# Main_Board.net
KiCad netlist of a schematic drawn in Altium Designer
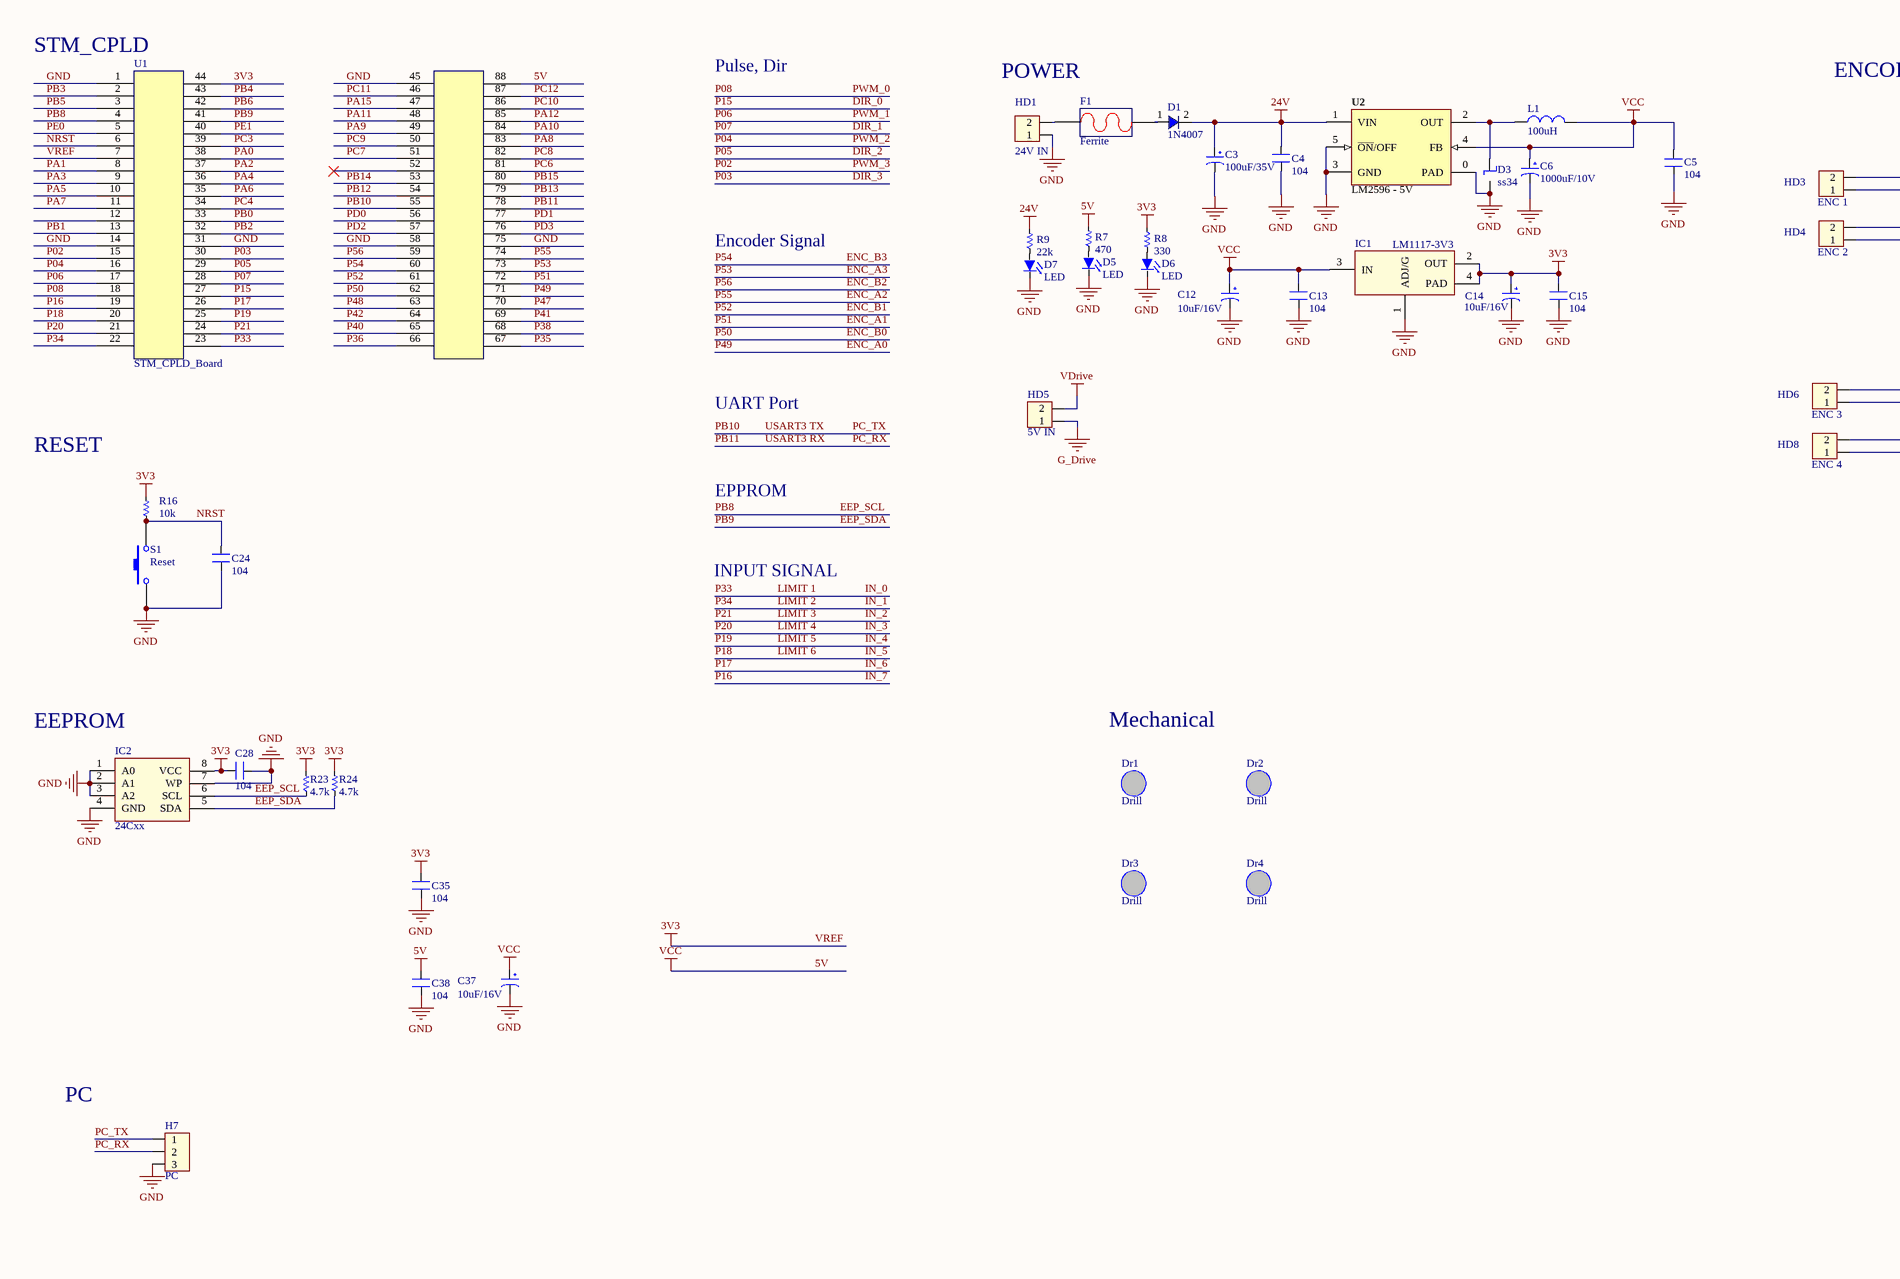
[diagram p0: Main_Board.SchDoc, top left]
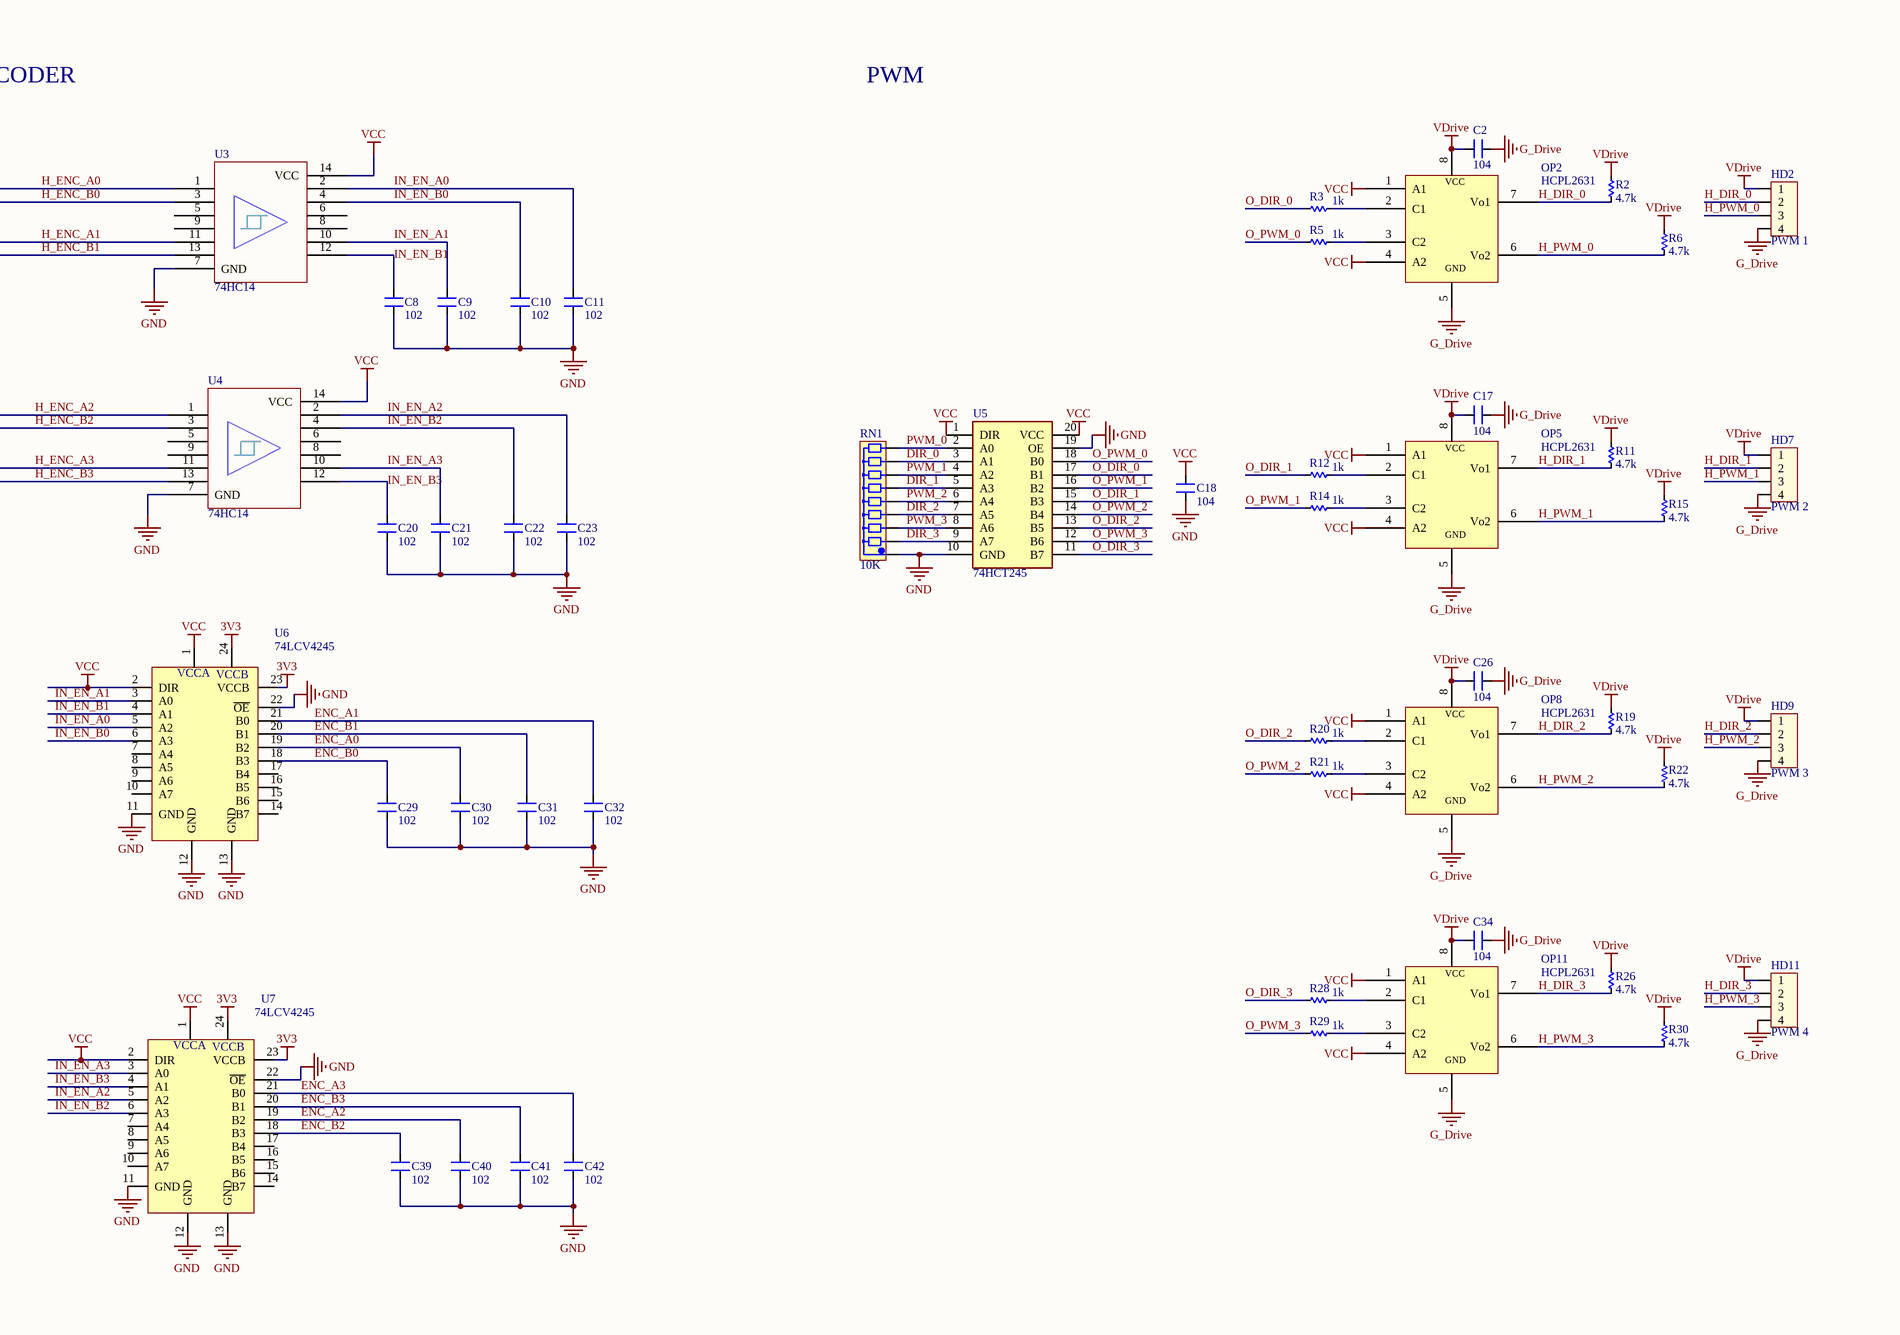
[diagram p1: Main_Board.SchDoc, top middle]
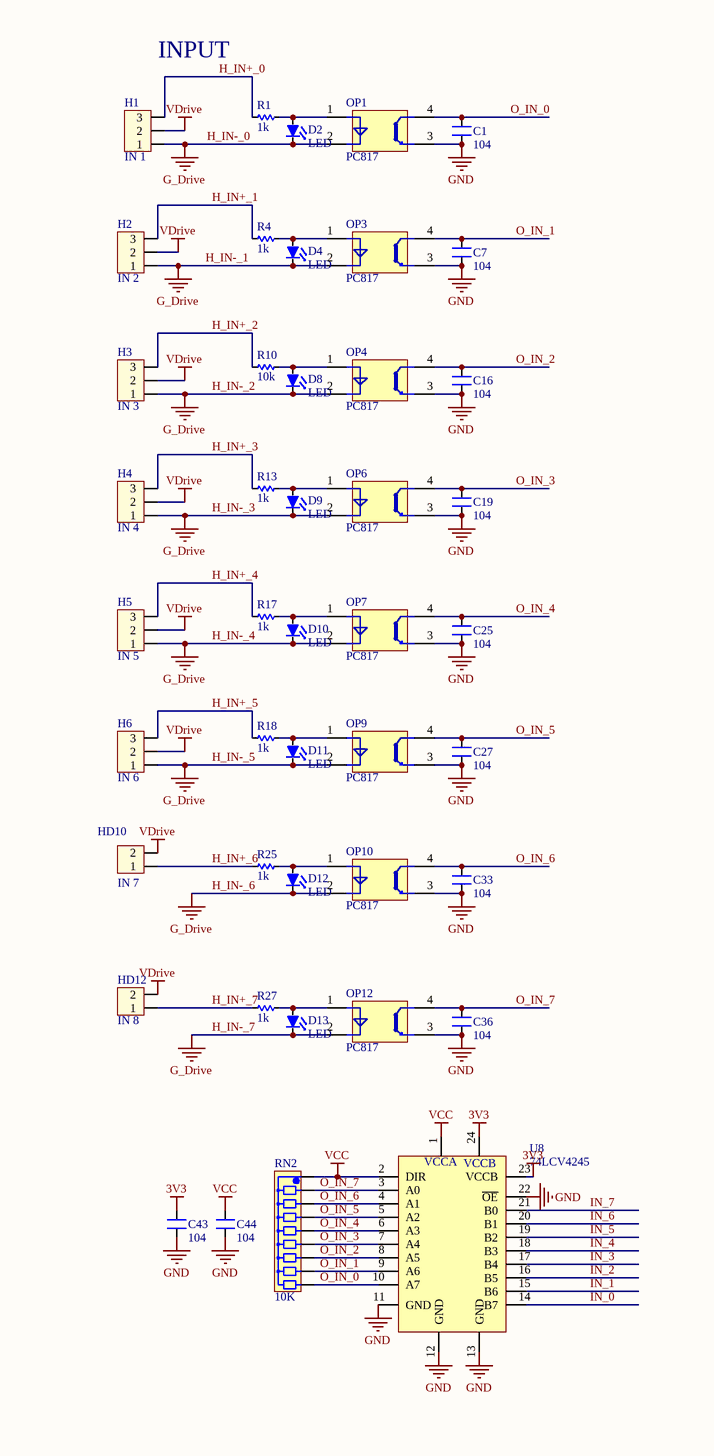
[diagram p2: Main_Board.SchDoc, top right]
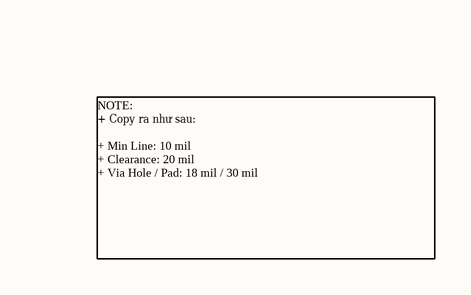
[diagram p3: Main_Board.SchDoc, bottom right]

(export (version "E")
  (design (tool "Eeschema 10.0.6"))
  (components
    (comp (ref "C1")
      (value "104")
      (footprint "CAP-SM-0805")
      (description "Ceramic Capacitor SMD")
      (libsource (lib "Main_Board") (part "CAP_SM_0805"))
    )
    (comp (ref "C2")
      (value "104")
      (footprint "CAP-SM-0805")
      (description "Ceramic Capacitor SMD")
      (libsource (lib "Main_Board") (part "CAP_SM_0805"))
    )
    (comp (ref "C3")
      (value "100uF/35V")
      (footprint "Cap_Alu_D8")
      (description "SMD Aluminum Electrolytic Capacitor")
      (libsource (lib "Main_Board") (part "Cap_SM_Alu"))
    )
    (comp (ref "C4")
      (value "104")
      (footprint "CAP-SM-0805")
      (description "Ceramic Capacitor SMD")
      (libsource (lib "Main_Board") (part "CAP_SM_0805"))
    )
    (comp (ref "C5")
      (value "104")
      (footprint "CAP-SM-0805")
      (description "Ceramic Capacitor SMD")
      (libsource (lib "Main_Board") (part "CAP_SM_0805"))
    )
    (comp (ref "C6")
      (value "1000uF/10V")
      (footprint "Cap_Alu_G")
      (description "SMD Aluminum Electrolytic Capacitor")
      (libsource (lib "Main_Board") (part "Cap_SM_Alu"))
    )
    (comp (ref "C7")
      (value "104")
      (footprint "CAP-SM-0805")
      (description "Ceramic Capacitor SMD")
      (libsource (lib "Main_Board") (part "CAP_SM_0805"))
    )
    (comp (ref "C8")
      (value "102")
      (footprint "CAP-SM-0805")
      (description "Ceramic Capacitor SMD")
      (libsource (lib "Main_Board") (part "CAP_SM_0805"))
    )
    (comp (ref "C9")
      (value "102")
      (footprint "CAP-SM-0805")
      (description "Ceramic Capacitor SMD")
      (libsource (lib "Main_Board") (part "CAP_SM_0805"))
    )
    (comp (ref "C10")
      (value "102")
      (footprint "CAP-SM-0805")
      (description "Ceramic Capacitor SMD")
      (libsource (lib "Main_Board") (part "CAP_SM_0805"))
    )
    (comp (ref "C11")
      (value "102")
      (footprint "CAP-SM-0805")
      (description "Ceramic Capacitor SMD")
      (libsource (lib "Main_Board") (part "CAP_SM_0805"))
    )
    (comp (ref "C12")
      (value "10uF/16V")
      (footprint "CAP_ALU_B")
      (description "C 47uF/50V , 220uF/16V")
      (libsource (lib "Main_Board") (part "CP2"))
    )
    (comp (ref "C13")
      (value "104")
      (footprint "CAP-SM-0805")
      (description "Ceramic Capacitor SMD")
      (libsource (lib "Main_Board") (part "CAP_SM_0805"))
    )
    (comp (ref "C14")
      (value "10uF/16V")
      (footprint "CAP_ALU_B")
      (description "C 47uF/50V , 220uF/16V")
      (libsource (lib "Main_Board") (part "CP2"))
    )
    (comp (ref "C15")
      (value "104")
      (footprint "CAP-SM-0805")
      (description "Ceramic Capacitor SMD")
      (libsource (lib "Main_Board") (part "CAP_SM_0805"))
    )
    (comp (ref "C16")
      (value "104")
      (footprint "CAP-SM-0805")
      (description "Ceramic Capacitor SMD")
      (libsource (lib "Main_Board") (part "CAP_SM_0805"))
    )
    (comp (ref "C17")
      (value "104")
      (footprint "CAP-SM-0805")
      (description "Ceramic Capacitor SMD")
      (libsource (lib "Main_Board") (part "CAP_SM_0805"))
    )
    (comp (ref "C18")
      (value "104")
      (footprint "CAP-SM-0805")
      (description "Ceramic Capacitor SMD")
      (libsource (lib "Main_Board") (part "CAP_SM_0805"))
    )
    (comp (ref "C19")
      (value "104")
      (footprint "CAP-SM-0805")
      (description "Ceramic Capacitor SMD")
      (libsource (lib "Main_Board") (part "CAP_SM_0805"))
    )
    (comp (ref "C20")
      (value "102")
      (footprint "CAP-SM-0805")
      (description "Ceramic Capacitor SMD")
      (libsource (lib "Main_Board") (part "CAP_SM_0805"))
    )
    (comp (ref "C21")
      (value "102")
      (footprint "CAP-SM-0805")
      (description "Ceramic Capacitor SMD")
      (libsource (lib "Main_Board") (part "CAP_SM_0805"))
    )
    (comp (ref "C22")
      (value "102")
      (footprint "CAP-SM-0805")
      (description "Ceramic Capacitor SMD")
      (libsource (lib "Main_Board") (part "CAP_SM_0805"))
    )
    (comp (ref "C23")
      (value "102")
      (footprint "CAP-SM-0805")
      (description "Ceramic Capacitor SMD")
      (libsource (lib "Main_Board") (part "CAP_SM_0805"))
    )
    (comp (ref "C24")
      (value "104")
      (footprint "CAP-SM-0805")
      (description "Ceramic Capacitor SMD")
      (libsource (lib "Main_Board") (part "CAP_SM_0805"))
    )
    (comp (ref "C25")
      (value "104")
      (footprint "CAP-SM-0805")
      (description "Ceramic Capacitor SMD")
      (libsource (lib "Main_Board") (part "CAP_SM_0805"))
    )
    (comp (ref "C26")
      (value "104")
      (footprint "CAP-SM-0805")
      (description "Ceramic Capacitor SMD")
      (libsource (lib "Main_Board") (part "CAP_SM_0805"))
    )
    (comp (ref "C27")
      (value "104")
      (footprint "CAP-SM-0805")
      (description "Ceramic Capacitor SMD")
      (libsource (lib "Main_Board") (part "CAP_SM_0805"))
    )
    (comp (ref "C28")
      (value "104")
      (footprint "CAP-SM-0805")
      (description "Ceramic Capacitor SMD")
      (libsource (lib "Main_Board") (part "CAP_SM_0805"))
    )
    (comp (ref "C29")
      (value "102")
      (footprint "CAP-SM-0805")
      (description "Ceramic Capacitor SMD")
      (libsource (lib "Main_Board") (part "CAP_SM_0805"))
    )
    (comp (ref "C30")
      (value "102")
      (footprint "CAP-SM-0805")
      (description "Ceramic Capacitor SMD")
      (libsource (lib "Main_Board") (part "CAP_SM_0805"))
    )
    (comp (ref "C31")
      (value "102")
      (footprint "CAP-SM-0805")
      (description "Ceramic Capacitor SMD")
      (libsource (lib "Main_Board") (part "CAP_SM_0805"))
    )
    (comp (ref "C32")
      (value "102")
      (footprint "CAP-SM-0805")
      (description "Ceramic Capacitor SMD")
      (libsource (lib "Main_Board") (part "CAP_SM_0805"))
    )
    (comp (ref "C33")
      (value "104")
      (footprint "CAP-SM-0805")
      (description "Ceramic Capacitor SMD")
      (libsource (lib "Main_Board") (part "CAP_SM_0805"))
    )
    (comp (ref "C34")
      (value "104")
      (footprint "CAP-SM-0805")
      (description "Ceramic Capacitor SMD")
      (libsource (lib "Main_Board") (part "CAP_SM_0805"))
    )
    (comp (ref "C35")
      (value "104")
      (footprint "CAP-SM-0805")
      (description "Ceramic Capacitor SMD")
      (libsource (lib "Main_Board") (part "CAP_SM_0805"))
    )
    (comp (ref "C36")
      (value "104")
      (footprint "CAP-SM-0805")
      (description "Ceramic Capacitor SMD")
      (libsource (lib "Main_Board") (part "CAP_SM_0805"))
    )
    (comp (ref "C37")
      (value "10uF/16V")
      (footprint "CAP_ALU_B")
      (description "C 47uF/50V , 220uF/16V")
      (libsource (lib "Main_Board") (part "CP2"))
    )
    (comp (ref "C38")
      (value "104")
      (footprint "CAP-SM-0805")
      (description "Ceramic Capacitor SMD")
      (libsource (lib "Main_Board") (part "CAP_SM_0805"))
    )
    (comp (ref "C39")
      (value "102")
      (footprint "CAP-SM-0805")
      (description "Ceramic Capacitor SMD")
      (libsource (lib "Main_Board") (part "CAP_SM_0805"))
    )
    (comp (ref "C40")
      (value "102")
      (footprint "CAP-SM-0805")
      (description "Ceramic Capacitor SMD")
      (libsource (lib "Main_Board") (part "CAP_SM_0805"))
    )
    (comp (ref "C41")
      (value "102")
      (footprint "CAP-SM-0805")
      (description "Ceramic Capacitor SMD")
      (libsource (lib "Main_Board") (part "CAP_SM_0805"))
    )
    (comp (ref "C42")
      (value "102")
      (footprint "CAP-SM-0805")
      (description "Ceramic Capacitor SMD")
      (libsource (lib "Main_Board") (part "CAP_SM_0805"))
    )
    (comp (ref "C43")
      (value "104")
      (footprint "CAP-SM-0805")
      (description "Ceramic Capacitor SMD")
      (libsource (lib "Main_Board") (part "CAP_SM_0805"))
    )
    (comp (ref "C44")
      (value "104")
      (footprint "CAP-SM-0805")
      (description "Ceramic Capacitor SMD")
      (libsource (lib "Main_Board") (part "CAP_SM_0805"))
    )
    (comp (ref "D1")
      (value "1N4007")
      (footprint "DO-214AB")
      (description "General Rectifier")
      (libsource (lib "Main_Board") (part "Diode"))
    )
    (comp (ref "D2")
      (value "LED")
      (footprint "LED_0805_Blue")
      (description "LED SMD")
      (libsource (lib "Main_Board") (part "LED_SMD"))
    )
    (comp (ref "D3")
      (value "ss34")
      (footprint "DO-214AB")
      (description "Surface Mount Schottky Barrier Rectifier")
      (libsource (lib "Main_Board") (part "ss34"))
    )
    (comp (ref "D4")
      (value "LED")
      (footprint "LED_0805_Blue")
      (description "LED SMD")
      (libsource (lib "Main_Board") (part "LED_SMD"))
    )
    (comp (ref "D5")
      (value "LED")
      (footprint "LED_0805_Blue")
      (description "LED SMD")
      (libsource (lib "Main_Board") (part "LED_SMD"))
    )
    (comp (ref "D6")
      (value "LED")
      (footprint "LED_0805_Blue")
      (description "LED SMD")
      (libsource (lib "Main_Board") (part "LED_SMD"))
    )
    (comp (ref "D7")
      (value "LED")
      (footprint "LED_0805_Blue")
      (description "LED SMD")
      (libsource (lib "Main_Board") (part "LED_SMD"))
    )
    (comp (ref "D8")
      (value "LED")
      (footprint "LED_0805_Blue")
      (description "LED SMD")
      (libsource (lib "Main_Board") (part "LED_SMD"))
    )
    (comp (ref "D9")
      (value "LED")
      (footprint "LED_0805_Blue")
      (description "LED SMD")
      (libsource (lib "Main_Board") (part "LED_SMD"))
    )
    (comp (ref "D10")
      (value "LED")
      (footprint "LED_0805_Blue")
      (description "LED SMD")
      (libsource (lib "Main_Board") (part "LED_SMD"))
    )
    (comp (ref "D11")
      (value "LED")
      (footprint "LED_0805_Blue")
      (description "LED SMD")
      (libsource (lib "Main_Board") (part "LED_SMD"))
    )
    (comp (ref "D12")
      (value "LED")
      (footprint "LED_0805_Blue")
      (description "LED SMD")
      (libsource (lib "Main_Board") (part "LED_SMD"))
    )
    (comp (ref "D13")
      (value "LED")
      (footprint "LED_0805_Blue")
      (description "LED SMD")
      (libsource (lib "Main_Board") (part "LED_SMD"))
    )
    (comp (ref "Dr1")
      (value "Drill")
      (footprint "Drill 3mm")
      (description "Drill 3mm")
      (libsource (lib "Main_Board") (part "Drill 3mm"))
    )
    (comp (ref "Dr2")
      (value "Drill")
      (footprint "Drill 3mm")
      (description "Drill 3mm")
      (libsource (lib "Main_Board") (part "Drill 3mm"))
    )
    (comp (ref "Dr3")
      (value "Drill")
      (footprint "Drill 3mm")
      (description "Drill 3mm")
      (libsource (lib "Main_Board") (part "Drill 3mm"))
    )
    (comp (ref "Dr4")
      (value "Drill")
      (footprint "Drill 3mm")
      (description "Drill 3mm")
      (libsource (lib "Main_Board") (part "Drill 3mm"))
    )
    (comp (ref "F1")
      (value "Ferrite")
      (footprint "Ferrite")
      (description "Ferrite bead")
      (libsource (lib "Main_Board") (part "Ferrite bead"))
    )
    (comp (ref "H1")
      (value "IN 1")
      (footprint "Header White 3")
      (description "Connector 3")
      (libsource (lib "") (part "Header white 3_1"))
    )
    (comp (ref "H2")
      (value "IN 2")
      (footprint "Header White 3")
      (description "Connector 3")
      (libsource (lib "") (part "Header white 3_1"))
    )
    (comp (ref "H3")
      (value "IN 3")
      (footprint "Header White 3")
      (description "Connector 3")
      (libsource (lib "") (part "Header white 3_1"))
    )
    (comp (ref "H4")
      (value "IN 4")
      (footprint "Header White 3")
      (description "Connector 3")
      (libsource (lib "") (part "Header white 3_1"))
    )
    (comp (ref "H5")
      (value "IN 5")
      (footprint "Header White 3")
      (description "Connector 3")
      (libsource (lib "") (part "Header white 3_1"))
    )
    (comp (ref "H6")
      (value "IN 6")
      (footprint "Header White 3")
      (description "Connector 3")
      (libsource (lib "") (part "Header white 3_1"))
    )
    (comp (ref "H7")
      (value "PC")
      (footprint "Header White 3")
      (description "Connector 3")
      (libsource (lib "Main_Board") (part "Header white 3"))
    )
    (comp (ref "HD1")
      (value "24V IN")
      (footprint "Domino 2")
      (description "Domino 2 200mil")
      (libsource (lib "Main_Board") (part "Domino 2"))
    )
    (comp (ref "HD2")
      (value "PWM 1")
      (footprint "Domino 4")
      (description "Domino 4 200mil")
      (libsource (lib "Main_Board") (part "Domino 4"))
    )
    (comp (ref "HD3")
      (value "ENC 1")
      (footprint "Domino 2")
      (description "Domino 2 200mil")
      (libsource (lib "Main_Board") (part "Domino 2"))
    )
    (comp (ref "HD4")
      (value "ENC 2")
      (footprint "Domino 2")
      (description "Domino 2 200mil")
      (libsource (lib "Main_Board") (part "Domino 2"))
    )
    (comp (ref "HD5")
      (value "5V IN")
      (footprint "Domino 2")
      (description "Domino 2 200mil")
      (libsource (lib "Main_Board") (part "Domino 2"))
    )
    (comp (ref "HD6")
      (value "ENC 3")
      (footprint "Domino 2")
      (description "Domino 2 200mil")
      (libsource (lib "Main_Board") (part "Domino 2"))
    )
    (comp (ref "HD7")
      (value "PWM 2")
      (footprint "Domino 4")
      (description "Domino 4 200mil")
      (libsource (lib "Main_Board") (part "Domino 4"))
    )
    (comp (ref "HD8")
      (value "ENC 4")
      (footprint "Domino 2")
      (description "Domino 2 200mil")
      (libsource (lib "Main_Board") (part "Domino 2"))
    )
    (comp (ref "HD9")
      (value "PWM 3")
      (footprint "Domino 4")
      (description "Domino 4 200mil")
      (libsource (lib "Main_Board") (part "Domino 4"))
    )
    (comp (ref "HD10")
      (value "IN 7")
      (footprint "Domino 2")
      (description "Domino 2 200mil")
      (libsource (lib "Main_Board") (part "Domino 2"))
    )
    (comp (ref "HD11")
      (value "PWM 4")
      (footprint "Domino 4")
      (description "Domino 4 200mil")
      (libsource (lib "Main_Board") (part "Domino 4"))
    )
    (comp (ref "HD12")
      (value "IN 8")
      (footprint "Domino 2")
      (description "Domino 2 200mil")
      (libsource (lib "Main_Board") (part "Domino 2"))
    )
    (comp (ref "IC1")
      (value "LM1117-3V3")
      (footprint "SOT223-4N")
      (description "Available in 1.8V, 2.5V, 2.85V, 3.3V, 5V, and  Adjustable Versions")
      (libsource (lib "Main_Board") (part "LM1117"))
    )
    (comp (ref "IC2")
      (value "24Cxx")
      (footprint "SOIC8")
      (description "Standard 2-Wire Bus Interface Serial EEPROM")
      (fields (field (name "COPYRIGHT BY") "VanDungEvn"))
      (libsource (lib "Main_Board") (part "24Cxx"))
    )
    (comp (ref "L1")
      (value "100uH")
      (footprint "INDUCTOR_SMD")
      (description "Inductor")
      (libsource (lib "Main_Board") (part "L1"))
    )
    (comp (ref "OP1")
      (value "PC817")
      (footprint "SOP4 2.54")
      (description "OPTO")
      (libsource (lib "Main_Board") (part "PC817"))
    )
    (comp (ref "OP2")
      (value "HCPL2631")
      (footprint "6N137SMD")
      (description "High CMR, High Speed TTL Compatible Optocouplers")
      (libsource (lib "Main_Board") (part "HCPL2631"))
    )
    (comp (ref "OP3")
      (value "PC817")
      (footprint "SOP4 2.54")
      (description "OPTO")
      (libsource (lib "Main_Board") (part "PC817"))
    )
    (comp (ref "OP4")
      (value "PC817")
      (footprint "SOP4 2.54")
      (description "OPTO")
      (libsource (lib "Main_Board") (part "PC817"))
    )
    (comp (ref "OP5")
      (value "HCPL2631")
      (footprint "6N137SMD")
      (description "High CMR, High Speed TTL Compatible Optocouplers")
      (libsource (lib "Main_Board") (part "HCPL2631"))
    )
    (comp (ref "OP6")
      (value "PC817")
      (footprint "SOP4 2.54")
      (description "OPTO")
      (libsource (lib "Main_Board") (part "PC817"))
    )
    (comp (ref "OP7")
      (value "PC817")
      (footprint "SOP4 2.54")
      (description "OPTO")
      (libsource (lib "Main_Board") (part "PC817"))
    )
    (comp (ref "OP8")
      (value "HCPL2631")
      (footprint "6N137SMD")
      (description "High CMR, High Speed TTL Compatible Optocouplers")
      (libsource (lib "Main_Board") (part "HCPL2631"))
    )
    (comp (ref "OP9")
      (value "PC817")
      (footprint "SOP4 2.54")
      (description "OPTO")
      (libsource (lib "Main_Board") (part "PC817"))
    )
    (comp (ref "OP10")
      (value "PC817")
      (footprint "SOP4 2.54")
      (description "OPTO")
      (libsource (lib "Main_Board") (part "PC817"))
    )
    (comp (ref "OP11")
      (value "HCPL2631")
      (footprint "6N137SMD")
      (description "High CMR, High Speed TTL Compatible Optocouplers")
      (libsource (lib "Main_Board") (part "HCPL2631"))
    )
    (comp (ref "OP12")
      (value "PC817")
      (footprint "SOP4 2.54")
      (description "OPTO")
      (libsource (lib "Main_Board") (part "PC817"))
    )
    (comp (ref "R1")
      (value "1k")
      (footprint "RES-SM-0805")
      (description "Resistor")
      (fields
        (field (name "MANUFACTURER") "Generic Components")
        (field (name "PUBLISHER") "Altium Hobart Technology Centre")
      )
      (libsource (lib "Main_Board") (part "Res-SMD"))
    )
    (comp (ref "R2")
      (value "4.7k")
      (footprint "RES-SM-0805")
      (description "Resistor")
      (fields
        (field (name "MANUFACTURER") "Generic Components")
        (field (name "PUBLISHER") "Altium Hobart Technology Centre")
      )
      (libsource (lib "Main_Board") (part "Res-SMD"))
    )
    (comp (ref "R3")
      (value "1k")
      (footprint "RES-SM-0805")
      (description "Resistor")
      (fields
        (field (name "MANUFACTURER") "Generic Components")
        (field (name "PUBLISHER") "Altium Hobart Technology Centre")
      )
      (libsource (lib "Main_Board") (part "Res-SMD"))
    )
    (comp (ref "R4")
      (value "1k")
      (footprint "RES-SM-0805")
      (description "Resistor")
      (fields
        (field (name "MANUFACTURER") "Generic Components")
        (field (name "PUBLISHER") "Altium Hobart Technology Centre")
      )
      (libsource (lib "Main_Board") (part "Res-SMD"))
    )
    (comp (ref "R5")
      (value "1k")
      (footprint "RES-SM-0805")
      (description "Resistor")
      (fields
        (field (name "MANUFACTURER") "Generic Components")
        (field (name "PUBLISHER") "Altium Hobart Technology Centre")
      )
      (libsource (lib "Main_Board") (part "Res-SMD"))
    )
    (comp (ref "R6")
      (value "4.7k")
      (footprint "RES-SM-0805")
      (description "Resistor")
      (fields
        (field (name "MANUFACTURER") "Generic Components")
        (field (name "PUBLISHER") "Altium Hobart Technology Centre")
      )
      (libsource (lib "Main_Board") (part "Res-SMD"))
    )
    (comp (ref "R7")
      (value "470")
      (footprint "RES-SM-0805")
      (description "Resistor")
      (fields
        (field (name "MANUFACTURER") "Generic Components")
        (field (name "PUBLISHER") "Altium Hobart Technology Centre")
      )
      (libsource (lib "Main_Board") (part "Res-SMD"))
    )
    (comp (ref "R8")
      (value "330")
      (footprint "RES-SM-0805")
      (description "Resistor")
      (fields
        (field (name "MANUFACTURER") "Generic Components")
        (field (name "PUBLISHER") "Altium Hobart Technology Centre")
      )
      (libsource (lib "Main_Board") (part "Res-SMD"))
    )
    (comp (ref "R9")
      (value "22k")
      (footprint "RES-SM-0805")
      (description "Resistor")
      (fields
        (field (name "MANUFACTURER") "Generic Components")
        (field (name "PUBLISHER") "Altium Hobart Technology Centre")
      )
      (libsource (lib "Main_Board") (part "Res-SMD"))
    )
    (comp (ref "R10")
      (value "10k")
      (footprint "RES-SM-0805")
      (description "Resistor")
      (fields
        (field (name "MANUFACTURER") "Generic Components")
        (field (name "PUBLISHER") "Altium Hobart Technology Centre")
      )
      (libsource (lib "Main_Board") (part "Res-SMD"))
    )
    (comp (ref "R11")
      (value "4.7k")
      (footprint "RES-SM-0805")
      (description "Resistor")
      (fields
        (field (name "MANUFACTURER") "Generic Components")
        (field (name "PUBLISHER") "Altium Hobart Technology Centre")
      )
      (libsource (lib "Main_Board") (part "Res-SMD"))
    )
    (comp (ref "R12")
      (value "1k")
      (footprint "RES-SM-0805")
      (description "Resistor")
      (fields
        (field (name "MANUFACTURER") "Generic Components")
        (field (name "PUBLISHER") "Altium Hobart Technology Centre")
      )
      (libsource (lib "Main_Board") (part "Res-SMD"))
    )
    (comp (ref "R13")
      (value "1k")
      (footprint "RES-SM-0805")
      (description "Resistor")
      (fields
        (field (name "MANUFACTURER") "Generic Components")
        (field (name "PUBLISHER") "Altium Hobart Technology Centre")
      )
      (libsource (lib "Main_Board") (part "Res-SMD"))
    )
    (comp (ref "R14")
      (value "1k")
      (footprint "RES-SM-0805")
      (description "Resistor")
      (fields
        (field (name "MANUFACTURER") "Generic Components")
        (field (name "PUBLISHER") "Altium Hobart Technology Centre")
      )
      (libsource (lib "Main_Board") (part "Res-SMD"))
    )
    (comp (ref "R15")
      (value "4.7k")
      (footprint "RES-SM-0805")
      (description "Resistor")
      (fields
        (field (name "MANUFACTURER") "Generic Components")
        (field (name "PUBLISHER") "Altium Hobart Technology Centre")
      )
      (libsource (lib "Main_Board") (part "Res-SMD"))
    )
    (comp (ref "R16")
      (value "10k")
      (footprint "RES-SM-0805")
      (description "Resistor")
      (fields
        (field (name "MANUFACTURER") "Generic Components")
        (field (name "PUBLISHER") "Altium Hobart Technology Centre")
      )
      (libsource (lib "Main_Board") (part "Res-SMD"))
    )
    (comp (ref "R17")
      (value "1k")
      (footprint "RES-SM-0805")
      (description "Resistor")
      (fields
        (field (name "MANUFACTURER") "Generic Components")
        (field (name "PUBLISHER") "Altium Hobart Technology Centre")
      )
      (libsource (lib "Main_Board") (part "Res-SMD"))
    )
    (comp (ref "R18")
      (value "1k")
      (footprint "RES-SM-0805")
      (description "Resistor")
      (fields
        (field (name "MANUFACTURER") "Generic Components")
        (field (name "PUBLISHER") "Altium Hobart Technology Centre")
      )
      (libsource (lib "Main_Board") (part "Res-SMD"))
    )
    (comp (ref "R19")
      (value "4.7k")
      (footprint "RES-SM-0805")
      (description "Resistor")
      (fields
        (field (name "MANUFACTURER") "Generic Components")
        (field (name "PUBLISHER") "Altium Hobart Technology Centre")
      )
      (libsource (lib "Main_Board") (part "Res-SMD"))
    )
    (comp (ref "R20")
      (value "1k")
      (footprint "RES-SM-0805")
      (description "Resistor")
      (fields
        (field (name "MANUFACTURER") "Generic Components")
        (field (name "PUBLISHER") "Altium Hobart Technology Centre")
      )
      (libsource (lib "Main_Board") (part "Res-SMD"))
    )
    (comp (ref "R21")
      (value "1k")
      (footprint "RES-SM-0805")
      (description "Resistor")
      (fields
        (field (name "MANUFACTURER") "Generic Components")
        (field (name "PUBLISHER") "Altium Hobart Technology Centre")
      )
      (libsource (lib "Main_Board") (part "Res-SMD"))
    )
    (comp (ref "R22")
      (value "4.7k")
      (footprint "RES-SM-0805")
      (description "Resistor")
      (fields
        (field (name "MANUFACTURER") "Generic Components")
        (field (name "PUBLISHER") "Altium Hobart Technology Centre")
      )
      (libsource (lib "Main_Board") (part "Res-SMD"))
    )
    (comp (ref "R23")
      (value "4.7k")
      (footprint "RES-SM-0805")
      (description "Resistor")
      (fields
        (field (name "MANUFACTURER") "Generic Components")
        (field (name "PUBLISHER") "Altium Hobart Technology Centre")
      )
      (libsource (lib "Main_Board") (part "Res-SMD"))
    )
    (comp (ref "R24")
      (value "4.7k")
      (footprint "RES-SM-0805")
      (description "Resistor")
      (fields
        (field (name "MANUFACTURER") "Generic Components")
        (field (name "PUBLISHER") "Altium Hobart Technology Centre")
      )
      (libsource (lib "Main_Board") (part "Res-SMD"))
    )
    (comp (ref "R25")
      (value "1k")
      (footprint "RES-SM-0805")
      (description "Resistor")
      (fields
        (field (name "MANUFACTURER") "Generic Components")
        (field (name "PUBLISHER") "Altium Hobart Technology Centre")
      )
      (libsource (lib "Main_Board") (part "Res-SMD"))
    )
    (comp (ref "R26")
      (value "4.7k")
      (footprint "RES-SM-0805")
      (description "Resistor")
      (fields
        (field (name "MANUFACTURER") "Generic Components")
        (field (name "PUBLISHER") "Altium Hobart Technology Centre")
      )
      (libsource (lib "Main_Board") (part "Res-SMD"))
    )
    (comp (ref "R27")
      (value "1k")
      (footprint "RES-SM-0805")
      (description "Resistor")
      (fields
        (field (name "MANUFACTURER") "Generic Components")
        (field (name "PUBLISHER") "Altium Hobart Technology Centre")
      )
      (libsource (lib "Main_Board") (part "Res-SMD"))
    )
    (comp (ref "R28")
      (value "1k")
      (footprint "RES-SM-0805")
      (description "Resistor")
      (fields
        (field (name "MANUFACTURER") "Generic Components")
        (field (name "PUBLISHER") "Altium Hobart Technology Centre")
      )
      (libsource (lib "Main_Board") (part "Res-SMD"))
    )
    (comp (ref "R29")
      (value "1k")
      (footprint "RES-SM-0805")
      (description "Resistor")
      (fields
        (field (name "MANUFACTURER") "Generic Components")
        (field (name "PUBLISHER") "Altium Hobart Technology Centre")
      )
      (libsource (lib "Main_Board") (part "Res-SMD"))
    )
    (comp (ref "R30")
      (value "4.7k")
      (footprint "RES-SM-0805")
      (description "Resistor")
      (fields
        (field (name "MANUFACTURER") "Generic Components")
        (field (name "PUBLISHER") "Altium Hobart Technology Centre")
      )
      (libsource (lib "Main_Board") (part "Res-SMD"))
    )
    (comp (ref "RN1")
      (value "10K")
      (footprint "RN8")
      (description "Resistor 8 (Thanh)")
      (libsource (lib "Main_Board") (part "RN8"))
    )
    (comp (ref "RN2")
      (value "10K")
      (footprint "RN8")
      (description "Resistor 8 (Thanh)")
      (libsource (lib "") (part "RN8_1"))
    )
    (comp (ref "S1")
      (value "Reset")
      (footprint "SW2")
      (description "Switch button 2 pin")
      (libsource (lib "Main_Board") (part "SW - 2Pin"))
    )
    (comp (ref "U1")
      (value "STM_CPLD_Board")
      (footprint "STM_CPLD_Board")
      (description "STM32f4 and Max2 570 on one board")
      (libsource (lib "Main_Board") (part "STM_CPLD_Board"))
    )
    (comp (ref "U2")
      (value "LM2596 - 5V")
      (footprint "TO263")
      (description "SIMPLE SWITCHER® Power Converter 150-kHz - 3A Step-Down Voltage Regulator")
      (libsource (lib "Main_Board") (part "LM2596"))
    )
    (comp (ref "U3")
      (value "74HC14")
      (footprint "SO14-150mil")
      (description "Hex Inverters With SCHMITT-TRIGGER Inputs")
      (libsource (lib "Main_Board") (part "74HC14"))
    )
    (comp (ref "U4")
      (value "74HC14")
      (footprint "SO14-150mil")
      (description "Hex Inverters With SCHMITT-TRIGGER Inputs")
      (libsource (lib "Main_Board") (part "74HC14"))
    )
    (comp (ref "U5")
      (value "74HCT245")
      (footprint "soic20")
      (description "Octal bus tranceiver")
      (libsource (lib "Main_Board") (part "74HC245"))
    )
    (comp (ref "U6")
      (value "74LCV4245")
      (footprint "SOIC24 - wide")
      (description "Octal dual supply translating transceiver; 3-state")
      (libsource (lib "Main_Board") (part "74LCV4245"))
    )
    (comp (ref "U7")
      (value "74LCV4245")
      (footprint "SOIC24 - wide")
      (description "Octal dual supply translating transceiver; 3-state")
      (libsource (lib "Main_Board") (part "74LCV4245"))
    )
    (comp (ref "U8")
      (value "74LCV4245")
      (footprint "SOIC24 - wide")
      (description "Octal dual supply translating transceiver; 3-state")
      (libsource (lib "Main_Board") (part "74LCV4245"))
    )
  )
  (nets
    (net (code "1") (name "/DIR_0") (class "Default")
      (node (ref "RN1") (pin "8") (pinfunction "8_8") (pintype "passive"))
      (node (ref "U1") (pin "27") (pinfunction "27_27") (pintype "passive"))
      (node (ref "U5") (pin "3") (pinfunction "A1_3") (pintype "passive"))
    )
    (net (code "2") (name "/DIR_1") (class "Default")
      (node (ref "RN1") (pin "6") (pinfunction "6_6") (pintype "passive"))
      (node (ref "U1") (pin "28") (pinfunction "28_28") (pintype "passive"))
      (node (ref "U5") (pin "5") (pinfunction "A3_5") (pintype "passive"))
    )
    (net (code "3") (name "/DIR_2") (class "Default")
      (node (ref "RN1") (pin "4") (pinfunction "4_4") (pintype "passive"))
      (node (ref "U1") (pin "29") (pinfunction "29_29") (pintype "passive"))
      (node (ref "U5") (pin "7") (pinfunction "A5_7") (pintype "passive"))
    )
    (net (code "4") (name "/DIR_3") (class "Default")
      (node (ref "RN1") (pin "2") (pinfunction "2_2") (pintype "passive"))
      (node (ref "U1") (pin "30") (pinfunction "30_30") (pintype "passive"))
      (node (ref "U5") (pin "9") (pinfunction "A7_9") (pintype "passive"))
    )
    (net (code "5") (name "/EEP_SCL") (class "Default")
      (node (ref "IC2") (pin "6") (pinfunction "SCL_6") (pintype "passive"))
      (node (ref "R23") (pin "1") (pinfunction "1_1") (pintype "passive"))
      (node (ref "U1") (pin "4") (pinfunction "4_4") (pintype "passive"))
    )
    (net (code "6") (name "/EEP_SDA") (class "Default")
      (node (ref "IC2") (pin "5") (pinfunction "SDA_5") (pintype "passive"))
      (node (ref "R24") (pin "2") (pinfunction "2_2") (pintype "passive"))
      (node (ref "U1") (pin "41") (pinfunction "41_41") (pintype "passive"))
    )
    (net (code "7") (name "/ENC_A0") (class "Default")
      (node (ref "C30") (pin "2") (pinfunction "2_2") (pintype "passive"))
      (node (ref "U1") (pin "71") (pinfunction "71_71") (pintype "passive"))
      (node (ref "U6") (pin "19") (pinfunction "B2_19") (pintype "passive"))
    )
    (net (code "8") (name "/ENC_A1") (class "Default")
      (node (ref "C32") (pin "2") (pinfunction "2_2") (pintype "passive"))
      (node (ref "U1") (pin "72") (pinfunction "72_72") (pintype "passive"))
      (node (ref "U6") (pin "21") (pinfunction "B0_21") (pintype "passive"))
    )
    (net (code "9") (name "/ENC_A2") (class "Default")
      (node (ref "C40") (pin "2") (pinfunction "2_2") (pintype "passive"))
      (node (ref "U1") (pin "74") (pinfunction "74_74") (pintype "passive"))
      (node (ref "U7") (pin "19") (pinfunction "B2_19") (pintype "passive"))
    )
    (net (code "10") (name "/ENC_A3") (class "Default")
      (node (ref "C42") (pin "2") (pinfunction "2_2") (pintype "passive"))
      (node (ref "U1") (pin "73") (pinfunction "73_73") (pintype "passive"))
      (node (ref "U7") (pin "21") (pinfunction "B0_21") (pintype "passive"))
    )
    (net (code "11") (name "/ENC_B0") (class "Default")
      (node (ref "C29") (pin "2") (pinfunction "2_2") (pintype "passive"))
      (node (ref "U1") (pin "62") (pinfunction "62_62") (pintype "passive"))
      (node (ref "U6") (pin "18") (pinfunction "B3_18") (pintype "passive"))
    )
    (net (code "12") (name "/ENC_B1") (class "Default")
      (node (ref "C31") (pin "2") (pinfunction "2_2") (pintype "passive"))
      (node (ref "U1") (pin "61") (pinfunction "61_61") (pintype "passive"))
      (node (ref "U6") (pin "20") (pinfunction "B1_20") (pintype "passive"))
    )
    (net (code "13") (name "/ENC_B2") (class "Default")
      (node (ref "C39") (pin "2") (pinfunction "2_2") (pintype "passive"))
      (node (ref "U1") (pin "59") (pinfunction "59_59") (pintype "passive"))
      (node (ref "U7") (pin "18") (pinfunction "B3_18") (pintype "passive"))
    )
    (net (code "14") (name "/ENC_B3") (class "Default")
      (node (ref "C41") (pin "2") (pinfunction "2_2") (pintype "passive"))
      (node (ref "U1") (pin "60") (pinfunction "60_60") (pintype "passive"))
      (node (ref "U7") (pin "20") (pinfunction "B1_20") (pintype "passive"))
    )
    (net (code "15") (name "/H_DIR_0") (class "Default")
      (node (ref "HD2") (pin "2") (pinfunction "2_2") (pintype "passive"))
      (node (ref "OP2") (pin "7") (pinfunction "Vo1_7") (pintype "passive"))
      (node (ref "R2") (pin "2") (pinfunction "2_2") (pintype "passive"))
    )
    (net (code "16") (name "/H_DIR_1") (class "Default")
      (node (ref "HD7") (pin "2") (pinfunction "2_2") (pintype "passive"))
      (node (ref "OP5") (pin "7") (pinfunction "Vo1_7") (pintype "passive"))
      (node (ref "R11") (pin "2") (pinfunction "2_2") (pintype "passive"))
    )
    (net (code "17") (name "/H_DIR_2") (class "Default")
      (node (ref "HD9") (pin "2") (pinfunction "2_2") (pintype "passive"))
      (node (ref "OP8") (pin "7") (pinfunction "Vo1_7") (pintype "passive"))
      (node (ref "R19") (pin "2") (pinfunction "2_2") (pintype "passive"))
    )
    (net (code "18") (name "/H_DIR_3") (class "Default")
      (node (ref "HD11") (pin "2") (pinfunction "2_2") (pintype "passive"))
      (node (ref "OP11") (pin "7") (pinfunction "Vo1_7") (pintype "passive"))
      (node (ref "R26") (pin "2") (pinfunction "2_2") (pintype "passive"))
    )
    (net (code "19") (name "/H_ENC_A0") (class "Default")
      (node (ref "HD3") (pin "2") (pinfunction "2_2") (pintype "passive"))
      (node (ref "U3") (pin "1") (pintype "passive"))
    )
    (net (code "20") (name "/H_ENC_A1") (class "Default")
      (node (ref "HD4") (pin "2") (pinfunction "2_2") (pintype "passive"))
      (node (ref "U3") (pin "11") (pinfunction "10_11") (pintype "passive"))
    )
    (net (code "21") (name "/H_ENC_A2") (class "Default")
      (node (ref "HD6") (pin "2") (pinfunction "2_2") (pintype "passive"))
      (node (ref "U4") (pin "1") (pintype "passive"))
    )
    (net (code "22") (name "/H_ENC_A3") (class "Default")
      (node (ref "HD8") (pin "2") (pinfunction "2_2") (pintype "passive"))
      (node (ref "U4") (pin "11") (pinfunction "10_11") (pintype "passive"))
    )
    (net (code "23") (name "/H_ENC_B0") (class "Default")
      (node (ref "HD3") (pin "1") (pinfunction "1_1") (pintype "passive"))
      (node (ref "U3") (pin "3") (pintype "passive"))
    )
    (net (code "24") (name "/H_ENC_B1") (class "Default")
      (node (ref "HD4") (pin "1") (pinfunction "1_1") (pintype "passive"))
      (node (ref "U3") (pin "13") (pinfunction "12_13") (pintype "passive"))
    )
    (net (code "25") (name "/H_ENC_B2") (class "Default")
      (node (ref "HD6") (pin "1") (pinfunction "1_1") (pintype "passive"))
      (node (ref "U4") (pin "3") (pintype "passive"))
    )
    (net (code "26") (name "/H_ENC_B3") (class "Default")
      (node (ref "HD8") (pin "1") (pinfunction "1_1") (pintype "passive"))
      (node (ref "U4") (pin "13") (pinfunction "12_13") (pintype "passive"))
    )
    (net (code "27") (name "/H_IN+_0") (class "Default")
      (node (ref "H1") (pin "3") (pinfunction "3_3") (pintype "passive"))
      (node (ref "R1") (pin "2") (pinfunction "2_2") (pintype "passive"))
    )
    (net (code "28") (name "/H_IN+_1") (class "Default")
      (node (ref "H2") (pin "3") (pinfunction "3_3") (pintype "passive"))
      (node (ref "R4") (pin "2") (pinfunction "2_2") (pintype "passive"))
    )
    (net (code "29") (name "/H_IN+_2") (class "Default")
      (node (ref "H3") (pin "3") (pinfunction "3_3") (pintype "passive"))
      (node (ref "R10") (pin "2") (pinfunction "2_2") (pintype "passive"))
    )
    (net (code "30") (name "/H_IN+_3") (class "Default")
      (node (ref "H4") (pin "3") (pinfunction "3_3") (pintype "passive"))
      (node (ref "R13") (pin "2") (pinfunction "2_2") (pintype "passive"))
    )
    (net (code "31") (name "/H_IN+_4") (class "Default")
      (node (ref "H5") (pin "3") (pinfunction "3_3") (pintype "passive"))
      (node (ref "R17") (pin "2") (pinfunction "2_2") (pintype "passive"))
    )
    (net (code "32") (name "/H_IN+_5") (class "Default")
      (node (ref "H6") (pin "3") (pinfunction "3_3") (pintype "passive"))
      (node (ref "R18") (pin "2") (pinfunction "2_2") (pintype "passive"))
    )
    (net (code "33") (name "/H_IN+_6") (class "Default")
      (node (ref "HD10") (pin "1") (pinfunction "1_1") (pintype "passive"))
      (node (ref "R25") (pin "2") (pinfunction "2_2") (pintype "passive"))
    )
    (net (code "34") (name "/H_IN+_7") (class "Default")
      (node (ref "HD12") (pin "1") (pinfunction "1_1") (pintype "passive"))
      (node (ref "R27") (pin "2") (pinfunction "2_2") (pintype "passive"))
    )
    (net (code "35") (name "/H_PWM_0") (class "Default")
      (node (ref "HD2") (pin "3") (pinfunction "3_3") (pintype "passive"))
      (node (ref "OP2") (pin "6") (pinfunction "Vo2_6") (pintype "passive"))
      (node (ref "R6") (pin "2") (pinfunction "2_2") (pintype "passive"))
    )
    (net (code "36") (name "/H_PWM_1") (class "Default")
      (node (ref "HD7") (pin "3") (pinfunction "3_3") (pintype "passive"))
      (node (ref "OP5") (pin "6") (pinfunction "Vo2_6") (pintype "passive"))
      (node (ref "R15") (pin "2") (pinfunction "2_2") (pintype "passive"))
    )
    (net (code "37") (name "/H_PWM_2") (class "Default")
      (node (ref "HD9") (pin "3") (pinfunction "3_3") (pintype "passive"))
      (node (ref "OP8") (pin "6") (pinfunction "Vo2_6") (pintype "passive"))
      (node (ref "R22") (pin "2") (pinfunction "2_2") (pintype "passive"))
    )
    (net (code "38") (name "/H_PWM_3") (class "Default")
      (node (ref "HD11") (pin "3") (pinfunction "3_3") (pintype "passive"))
      (node (ref "OP11") (pin "6") (pinfunction "Vo2_6") (pintype "passive"))
      (node (ref "R30") (pin "2") (pinfunction "2_2") (pintype "passive"))
    )
    (net (code "39") (name "/IN_0") (class "Default")
      (node (ref "U1") (pin "23") (pinfunction "23_23") (pintype "passive"))
      (node (ref "U8") (pin "14") (pinfunction "B7_14") (pintype "passive"))
    )
    (net (code "40") (name "/IN_1") (class "Default")
      (node (ref "U1") (pin "22") (pinfunction "22_22") (pintype "passive"))
      (node (ref "U8") (pin "15") (pinfunction "B6_15") (pintype "passive"))
    )
    (net (code "41") (name "/IN_2") (class "Default")
      (node (ref "U1") (pin "24") (pinfunction "24_24") (pintype "passive"))
      (node (ref "U8") (pin "16") (pinfunction "B5_16") (pintype "passive"))
    )
    (net (code "42") (name "/IN_3") (class "Default")
      (node (ref "U1") (pin "21") (pinfunction "21_21") (pintype "passive"))
      (node (ref "U8") (pin "17") (pinfunction "B4_17") (pintype "passive"))
    )
    (net (code "43") (name "/IN_4") (class "Default")
      (node (ref "U1") (pin "25") (pinfunction "25_25") (pintype "passive"))
      (node (ref "U8") (pin "18") (pinfunction "B3_18") (pintype "passive"))
    )
    (net (code "44") (name "/IN_5") (class "Default")
      (node (ref "U1") (pin "20") (pinfunction "20_20") (pintype "passive"))
      (node (ref "U8") (pin "19") (pinfunction "B2_19") (pintype "passive"))
    )
    (net (code "45") (name "/IN_6") (class "Default")
      (node (ref "U1") (pin "26") (pinfunction "26_26") (pintype "passive"))
      (node (ref "U8") (pin "20") (pinfunction "B1_20") (pintype "passive"))
    )
    (net (code "46") (name "/IN_7") (class "Default")
      (node (ref "U1") (pin "19") (pinfunction "19_19") (pintype "passive"))
      (node (ref "U8") (pin "21") (pinfunction "B0_21") (pintype "passive"))
    )
    (net (code "47") (name "/IN_EN_A0") (class "Default")
      (node (ref "C11") (pin "2") (pinfunction "2_2") (pintype "passive"))
      (node (ref "U3") (pin "2") (pintype "passive"))
      (node (ref "U6") (pin "5") (pinfunction "A2_5") (pintype "passive"))
    )
    (net (code "48") (name "/IN_EN_A1") (class "Default")
      (node (ref "C9") (pin "2") (pinfunction "2_2") (pintype "passive"))
      (node (ref "U3") (pin "10") (pinfunction "9_10") (pintype "passive"))
      (node (ref "U6") (pin "3") (pinfunction "A0_3") (pintype "passive"))
    )
    (net (code "49") (name "/IN_EN_A2") (class "Default")
      (node (ref "C23") (pin "2") (pinfunction "2_2") (pintype "passive"))
      (node (ref "U4") (pin "2") (pintype "passive"))
      (node (ref "U7") (pin "5") (pinfunction "A2_5") (pintype "passive"))
    )
    (net (code "50") (name "/IN_EN_A3") (class "Default")
      (node (ref "C21") (pin "2") (pinfunction "2_2") (pintype "passive"))
      (node (ref "U4") (pin "10") (pinfunction "9_10") (pintype "passive"))
      (node (ref "U7") (pin "3") (pinfunction "A0_3") (pintype "passive"))
    )
    (net (code "51") (name "/IN_EN_B0") (class "Default")
      (node (ref "C10") (pin "2") (pinfunction "2_2") (pintype "passive"))
      (node (ref "U3") (pin "4") (pintype "passive"))
      (node (ref "U6") (pin "6") (pinfunction "A3_6") (pintype "passive"))
    )
    (net (code "52") (name "/IN_EN_B1") (class "Default")
      (node (ref "C8") (pin "2") (pinfunction "2_2") (pintype "passive"))
      (node (ref "U3") (pin "12") (pinfunction "11_12") (pintype "passive"))
      (node (ref "U6") (pin "4") (pinfunction "A1_4") (pintype "passive"))
    )
    (net (code "53") (name "/IN_EN_B2") (class "Default")
      (node (ref "C22") (pin "2") (pinfunction "2_2") (pintype "passive"))
      (node (ref "U4") (pin "4") (pintype "passive"))
      (node (ref "U7") (pin "6") (pinfunction "A3_6") (pintype "passive"))
    )
    (net (code "54") (name "/IN_EN_B3") (class "Default")
      (node (ref "C20") (pin "2") (pinfunction "2_2") (pintype "passive"))
      (node (ref "U4") (pin "12") (pinfunction "11_12") (pintype "passive"))
      (node (ref "U7") (pin "4") (pinfunction "A1_4") (pintype "passive"))
    )
    (net (code "55") (name "/NRST") (class "Default")
      (node (ref "C24") (pin "1") (pinfunction "1_1") (pintype "passive"))
      (node (ref "R16") (pin "2") (pinfunction "2_2") (pintype "passive"))
      (node (ref "S1") (pin "2") (pinfunction "2_2") (pintype "passive"))
      (node (ref "U1") (pin "6") (pinfunction "6_6") (pintype "passive"))
    )
    (net (code "56") (name "/O_DIR_0") (class "Default")
      (node (ref "R3") (pin "1") (pinfunction "1_1") (pintype "passive"))
      (node (ref "U5") (pin "17") (pinfunction "B1_17") (pintype "passive"))
    )
    (net (code "57") (name "/O_DIR_1") (class "Default")
      (node (ref "R12") (pin "1") (pinfunction "1_1") (pintype "passive"))
      (node (ref "U5") (pin "15") (pinfunction "B3_15") (pintype "passive"))
    )
    (net (code "58") (name "/O_DIR_2") (class "Default")
      (node (ref "R20") (pin "1") (pinfunction "1_1") (pintype "passive"))
      (node (ref "U5") (pin "13") (pinfunction "B5_13") (pintype "passive"))
    )
    (net (code "59") (name "/O_DIR_3") (class "Default")
      (node (ref "R28") (pin "1") (pinfunction "1_1") (pintype "passive"))
      (node (ref "U5") (pin "11") (pinfunction "B7_11") (pintype "passive"))
    )
    (net (code "60") (name "/O_IN_0") (class "Default")
      (node (ref "C1") (pin "2") (pinfunction "2_2") (pintype "passive"))
      (node (ref "OP1") (pin "4") (pinfunction "E_4") (pintype "passive"))
      (node (ref "RN2") (pin "9") (pinfunction "9_9") (pintype "passive"))
      (node (ref "U8") (pin "10") (pinfunction "A7_10") (pintype "passive"))
    )
    (net (code "61") (name "/O_IN_1") (class "Default")
      (node (ref "C7") (pin "2") (pinfunction "2_2") (pintype "passive"))
      (node (ref "OP3") (pin "4") (pinfunction "E_4") (pintype "passive"))
      (node (ref "RN2") (pin "8") (pinfunction "8_8") (pintype "passive"))
      (node (ref "U8") (pin "9") (pinfunction "A6_9") (pintype "passive"))
    )
    (net (code "62") (name "/O_IN_2") (class "Default")
      (node (ref "C16") (pin "2") (pinfunction "2_2") (pintype "passive"))
      (node (ref "OP4") (pin "4") (pinfunction "E_4") (pintype "passive"))
      (node (ref "RN2") (pin "7") (pinfunction "7_7") (pintype "passive"))
      (node (ref "U8") (pin "8") (pinfunction "A5_8") (pintype "passive"))
    )
    (net (code "63") (name "/O_IN_3") (class "Default")
      (node (ref "C19") (pin "2") (pinfunction "2_2") (pintype "passive"))
      (node (ref "OP6") (pin "4") (pinfunction "E_4") (pintype "passive"))
      (node (ref "RN2") (pin "6") (pinfunction "6_6") (pintype "passive"))
      (node (ref "U8") (pin "7") (pinfunction "A4_7") (pintype "passive"))
    )
    (net (code "64") (name "/O_IN_4") (class "Default")
      (node (ref "C25") (pin "2") (pinfunction "2_2") (pintype "passive"))
      (node (ref "OP7") (pin "4") (pinfunction "E_4") (pintype "passive"))
      (node (ref "RN2") (pin "5") (pinfunction "5_5") (pintype "passive"))
      (node (ref "U8") (pin "6") (pinfunction "A3_6") (pintype "passive"))
    )
    (net (code "65") (name "/O_IN_5") (class "Default")
      (node (ref "C27") (pin "2") (pinfunction "2_2") (pintype "passive"))
      (node (ref "OP9") (pin "4") (pinfunction "E_4") (pintype "passive"))
      (node (ref "RN2") (pin "4") (pinfunction "4_4") (pintype "passive"))
      (node (ref "U8") (pin "5") (pinfunction "A2_5") (pintype "passive"))
    )
    (net (code "66") (name "/O_IN_6") (class "Default")
      (node (ref "C33") (pin "2") (pinfunction "2_2") (pintype "passive"))
      (node (ref "OP10") (pin "4") (pinfunction "E_4") (pintype "passive"))
      (node (ref "RN2") (pin "3") (pinfunction "3_3") (pintype "passive"))
      (node (ref "U8") (pin "4") (pinfunction "A1_4") (pintype "passive"))
    )
    (net (code "67") (name "/O_IN_7") (class "Default")
      (node (ref "C36") (pin "2") (pinfunction "2_2") (pintype "passive"))
      (node (ref "OP12") (pin "4") (pinfunction "E_4") (pintype "passive"))
      (node (ref "RN2") (pin "2") (pinfunction "2_2") (pintype "passive"))
      (node (ref "U8") (pin "3") (pinfunction "A0_3") (pintype "passive"))
    )
    (net (code "68") (name "/O_PWM_0") (class "Default")
      (node (ref "R5") (pin "1") (pinfunction "1_1") (pintype "passive"))
      (node (ref "U5") (pin "18") (pinfunction "B0_18") (pintype "passive"))
    )
    (net (code "69") (name "/O_PWM_1") (class "Default")
      (node (ref "R14") (pin "1") (pinfunction "1_1") (pintype "passive"))
      (node (ref "U5") (pin "16") (pinfunction "B2_16") (pintype "passive"))
    )
    (net (code "70") (name "/O_PWM_2") (class "Default")
      (node (ref "R21") (pin "1") (pinfunction "1_1") (pintype "passive"))
      (node (ref "U5") (pin "14") (pinfunction "B4_14") (pintype "passive"))
    )
    (net (code "71") (name "/O_PWM_3") (class "Default")
      (node (ref "R29") (pin "1") (pinfunction "1_1") (pintype "passive"))
      (node (ref "U5") (pin "12") (pinfunction "B6_12") (pintype "passive"))
    )
    (net (code "72") (name "/P02") (class "Default")
      (node (ref "RN1") (pin "3") (pinfunction "3_3") (pintype "passive"))
      (node (ref "U1") (pin "15") (pinfunction "15_15") (pintype "passive"))
      (node (ref "U5") (pin "8") (pinfunction "A6_8") (pintype "passive"))
    )
    (net (code "73") (name "/P04") (class "Default")
      (node (ref "RN1") (pin "5") (pinfunction "5_5") (pintype "passive"))
      (node (ref "U1") (pin "16") (pinfunction "16_16") (pintype "passive"))
      (node (ref "U5") (pin "6") (pinfunction "A4_6") (pintype "passive"))
    )
    (net (code "74") (name "/P06") (class "Default")
      (node (ref "RN1") (pin "7") (pinfunction "7_7") (pintype "passive"))
      (node (ref "U1") (pin "17") (pinfunction "17_17") (pintype "passive"))
      (node (ref "U5") (pin "4") (pinfunction "A2_4") (pintype "passive"))
    )
    (net (code "75") (name "/P08") (class "Default")
      (node (ref "RN1") (pin "9") (pinfunction "9_9") (pintype "passive"))
      (node (ref "U1") (pin "18") (pinfunction "18_18") (pintype "passive"))
      (node (ref "U5") (pin "2") (pinfunction "A0_2") (pintype "passive"))
    )
    (net (code "76") (name "/P35") (class "Default")
      (node (ref "U1") (pin "67") (pinfunction "67_67") (pintype "passive"))
    )
    (net (code "77") (name "/P36") (class "Default")
      (node (ref "U1") (pin "66") (pinfunction "66_66") (pintype "passive"))
    )
    (net (code "78") (name "/P38") (class "Default")
      (node (ref "U1") (pin "68") (pinfunction "68_68") (pintype "passive"))
    )
    (net (code "79") (name "/P40") (class "Default")
      (node (ref "U1") (pin "65") (pinfunction "65_65") (pintype "passive"))
    )
    (net (code "80") (name "/P41") (class "Default")
      (node (ref "U1") (pin "69") (pinfunction "69_69") (pintype "passive"))
    )
    (net (code "81") (name "/P42") (class "Default")
      (node (ref "U1") (pin "64") (pinfunction "64_64") (pintype "passive"))
    )
    (net (code "82") (name "/P47") (class "Default")
      (node (ref "U1") (pin "70") (pinfunction "70_70") (pintype "passive"))
    )
    (net (code "83") (name "/P48") (class "Default")
      (node (ref "U1") (pin "63") (pinfunction "63_63") (pintype "passive"))
    )
    (net (code "84") (name "/PA0") (class "Default")
      (node (ref "U1") (pin "38") (pinfunction "38_38") (pintype "passive"))
    )
    (net (code "85") (name "/PA1") (class "Default")
      (node (ref "U1") (pin "8") (pinfunction "8_8") (pintype "passive"))
    )
    (net (code "86") (name "/PA2") (class "Default")
      (node (ref "U1") (pin "37") (pinfunction "37_37") (pintype "passive"))
    )
    (net (code "87") (name "/PA3") (class "Default")
      (node (ref "U1") (pin "9") (pinfunction "9_9") (pintype "passive"))
    )
    (net (code "88") (name "/PA4") (class "Default")
      (node (ref "U1") (pin "36") (pinfunction "36_36") (pintype "passive"))
    )
    (net (code "89") (name "/PA5") (class "Default")
      (node (ref "U1") (pin "10") (pinfunction "10_10") (pintype "passive"))
    )
    (net (code "90") (name "/PA6") (class "Default")
      (node (ref "U1") (pin "35") (pinfunction "35_35") (pintype "passive"))
    )
    (net (code "91") (name "/PA7") (class "Default")
      (node (ref "U1") (pin "11") (pinfunction "11_11") (pintype "passive"))
    )
    (net (code "92") (name "/PA8") (class "Default")
      (node (ref "U1") (pin "83") (pinfunction "83_83") (pintype "passive"))
    )
    (net (code "93") (name "/PA9") (class "Default")
      (node (ref "U1") (pin "49") (pinfunction "49_49") (pintype "passive"))
    )
    (net (code "94") (name "/PA10") (class "Default")
      (node (ref "U1") (pin "84") (pinfunction "84_84") (pintype "passive"))
    )
    (net (code "95") (name "/PA11") (class "Default")
      (node (ref "U1") (pin "48") (pinfunction "48_48") (pintype "passive"))
    )
    (net (code "96") (name "/PA12") (class "Default")
      (node (ref "U1") (pin "85") (pinfunction "85_85") (pintype "passive"))
    )
    (net (code "97") (name "/PA15") (class "Default")
      (node (ref "U1") (pin "47") (pinfunction "47_47") (pintype "passive"))
    )
    (net (code "98") (name "/PB0") (class "Default")
      (node (ref "U1") (pin "33") (pinfunction "33_33") (pintype "passive"))
    )
    (net (code "99") (name "/PB1") (class "Default")
      (node (ref "U1") (pin "13") (pinfunction "13_13") (pintype "passive"))
    )
    (net (code "100") (name "/PB2") (class "Default")
      (node (ref "U1") (pin "32") (pinfunction "32_32") (pintype "passive"))
    )
    (net (code "101") (name "/PB3") (class "Default")
      (node (ref "U1") (pin "2") (pinfunction "2_2") (pintype "passive"))
    )
    (net (code "102") (name "/PB4") (class "Default")
      (node (ref "U1") (pin "43") (pinfunction "43_43") (pintype "passive"))
    )
    (net (code "103") (name "/PB5") (class "Default")
      (node (ref "U1") (pin "3") (pinfunction "3_3") (pintype "passive"))
    )
    (net (code "104") (name "/PB6") (class "Default")
      (node (ref "U1") (pin "42") (pinfunction "42_42") (pintype "passive"))
    )
    (net (code "105") (name "/PB10") (class "Default")
      (node (ref "H7") (pin "1") (pinfunction "1_1") (pintype "passive"))
      (node (ref "U1") (pin "55") (pinfunction "55_55") (pintype "passive"))
    )
    (net (code "106") (name "/PB11") (class "Default")
      (node (ref "H7") (pin "2") (pinfunction "2_2") (pintype "passive"))
      (node (ref "U1") (pin "78") (pinfunction "78_78") (pintype "passive"))
    )
    (net (code "107") (name "/PB12") (class "Default")
      (node (ref "U1") (pin "54") (pinfunction "54_54") (pintype "passive"))
    )
    (net (code "108") (name "/PB13") (class "Default")
      (node (ref "U1") (pin "79") (pinfunction "79_79") (pintype "passive"))
    )
    (net (code "109") (name "/PB14") (class "Default")
      (node (ref "U1") (pin "53") (pinfunction "53_53") (pintype "passive"))
    )
    (net (code "110") (name "/PB15") (class "Default")
      (node (ref "U1") (pin "80") (pinfunction "80_80") (pintype "passive"))
    )
    (net (code "111") (name "/PC3") (class "Default")
      (node (ref "U1") (pin "39") (pinfunction "39_39") (pintype "passive"))
    )
    (net (code "112") (name "/PC4") (class "Default")
      (node (ref "U1") (pin "34") (pinfunction "34_34") (pintype "passive"))
    )
    (net (code "113") (name "/PC6") (class "Default")
      (node (ref "U1") (pin "81") (pinfunction "81_81") (pintype "passive"))
    )
    (net (code "114") (name "/PC7") (class "Default")
      (node (ref "U1") (pin "51") (pinfunction "51_51") (pintype "passive"))
    )
    (net (code "115") (name "/PC8") (class "Default")
      (node (ref "U1") (pin "82") (pinfunction "82_82") (pintype "passive"))
    )
    (net (code "116") (name "/PC9") (class "Default")
      (node (ref "U1") (pin "50") (pinfunction "50_50") (pintype "passive"))
    )
    (net (code "117") (name "/PC10") (class "Default")
      (node (ref "U1") (pin "86") (pinfunction "86_86") (pintype "passive"))
    )
    (net (code "118") (name "/PC11") (class "Default")
      (node (ref "U1") (pin "46") (pinfunction "46_46") (pintype "passive"))
    )
    (net (code "119") (name "/PC12") (class "Default")
      (node (ref "U1") (pin "87") (pinfunction "87_87") (pintype "passive"))
    )
    (net (code "120") (name "/PD0") (class "Default")
      (node (ref "U1") (pin "56") (pinfunction "56_56") (pintype "passive"))
    )
    (net (code "121") (name "/PD1") (class "Default")
      (node (ref "U1") (pin "77") (pinfunction "77_77") (pintype "passive"))
    )
    (net (code "122") (name "/PD2") (class "Default")
      (node (ref "U1") (pin "57") (pinfunction "57_57") (pintype "passive"))
    )
    (net (code "123") (name "/PD3") (class "Default")
      (node (ref "U1") (pin "76") (pinfunction "76_76") (pintype "passive"))
    )
    (net (code "124") (name "/PE0") (class "Default")
      (node (ref "U1") (pin "5") (pinfunction "5_5") (pintype "passive"))
    )
    (net (code "125") (name "/PE1") (class "Default")
      (node (ref "U1") (pin "40") (pinfunction "40_40") (pintype "passive"))
    )
    (net (code "126") (name "3V3") (class "Default")
      (node (ref "C14") (pin "1") (pinfunction "1_1") (pintype "passive"))
      (node (ref "C15") (pin "1") (pinfunction "1_1") (pintype "passive"))
      (node (ref "C28") (pin "2") (pinfunction "2_2") (pintype "passive"))
      (node (ref "C35") (pin "1") (pinfunction "1_1") (pintype "passive"))
      (node (ref "C43") (pin "2") (pinfunction "2_2") (pintype "passive"))
      (node (ref "IC1") (pin "2") (pinfunction "OUT_2") (pintype "passive"))
      (node (ref "IC1") (pin "4") (pinfunction "PAD_4") (pintype "passive"))
      (node (ref "IC2") (pin "8") (pinfunction "VCC_8") (pintype "power_in"))
      (node (ref "R16") (pin "1") (pinfunction "1_1") (pintype "passive"))
      (node (ref "R23") (pin "2") (pinfunction "2_2") (pintype "passive"))
      (node (ref "R24") (pin "1") (pinfunction "1_1") (pintype "passive"))
      (node (ref "R8") (pin "1") (pinfunction "1_1") (pintype "passive"))
      (node (ref "U1") (pin "44") (pinfunction "44_44") (pintype "passive"))
      (node (ref "U1") (pin "7") (pinfunction "7_7") (pintype "passive"))
      (node (ref "U6") (pin "23") (pinfunction "VCCB_23") (pintype "passive"))
      (node (ref "U6") (pin "24") (pinfunction "VCC(B)_24") (pintype "passive"))
      (node (ref "U7") (pin "23") (pinfunction "VCCB_23") (pintype "passive"))
      (node (ref "U7") (pin "24") (pinfunction "VCC(B)_24") (pintype "passive"))
      (node (ref "U8") (pin "23") (pinfunction "VCCB_23") (pintype "passive"))
      (node (ref "U8") (pin "24") (pinfunction "VCC(B)_24") (pintype "passive"))
    )
    (net (code "127") (name "5V") (class "Default")
      (node (ref "C12") (pin "1") (pinfunction "1_1") (pintype "passive"))
      (node (ref "C13") (pin "1") (pinfunction "1_1") (pintype "passive"))
      (node (ref "C18") (pin "2") (pinfunction "2_2") (pintype "passive"))
      (node (ref "C37") (pin "1") (pinfunction "1_1") (pintype "passive"))
      (node (ref "C38") (pin "1") (pinfunction "1_1") (pintype "passive"))
      (node (ref "C44") (pin "2") (pinfunction "2_2") (pintype "passive"))
      (node (ref "C5") (pin "2") (pinfunction "2_2") (pintype "passive"))
      (node (ref "C6") (pin "1") (pinfunction "1_1") (pintype "passive"))
      (node (ref "IC1") (pin "3") (pinfunction "IN_3") (pintype "passive"))
      (node (ref "L1") (pin "2") (pinfunction "2_2") (pintype "passive"))
      (node (ref "OP11") (pin "1") (pinfunction "A1_1") (pintype "passive"))
      (node (ref "OP11") (pin "4") (pinfunction "A2_4") (pintype "passive"))
      (node (ref "OP2") (pin "1") (pinfunction "A1_1") (pintype "passive"))
      (node (ref "OP2") (pin "4") (pinfunction "A2_4") (pintype "passive"))
      (node (ref "OP5") (pin "1") (pinfunction "A1_1") (pintype "passive"))
      (node (ref "OP5") (pin "4") (pinfunction "A2_4") (pintype "passive"))
      (node (ref "OP8") (pin "1") (pinfunction "A1_1") (pintype "passive"))
      (node (ref "OP8") (pin "4") (pinfunction "A2_4") (pintype "passive"))
      (node (ref "R7") (pin "1") (pinfunction "1_1") (pintype "passive"))
      (node (ref "RN2") (pin "1") (pinfunction "1_1") (pintype "passive"))
      (node (ref "U1") (pin "88") (pinfunction "88_88") (pintype "passive"))
      (node (ref "U2") (pin "4") (pinfunction "FB_4") (pintype "input"))
      (node (ref "U3") (pin "14") (pinfunction "VCC_14") (pintype "passive"))
      (node (ref "U4") (pin "14") (pinfunction "VCC_14") (pintype "passive"))
      (node (ref "U5") (pin "1") (pinfunction "DIR_1") (pintype "passive"))
      (node (ref "U5") (pin "20") (pinfunction "VCC_20") (pintype "power_in"))
      (node (ref "U6") (pin "1") (pinfunction "VCC(A)_1") (pintype "passive"))
      (node (ref "U6") (pin "2") (pinfunction "DIR_2") (pintype "passive"))
      (node (ref "U7") (pin "1") (pinfunction "VCC(A)_1") (pintype "passive"))
      (node (ref "U7") (pin "2") (pinfunction "DIR_2") (pintype "passive"))
      (node (ref "U8") (pin "1") (pinfunction "VCC(A)_1") (pintype "passive"))
      (node (ref "U8") (pin "2") (pinfunction "DIR_2") (pintype "passive"))
    )
    (net (code "128") (name "24V") (class "Default")
      (node (ref "C3") (pin "1") (pinfunction "1_1") (pintype "passive"))
      (node (ref "C4") (pin "1") (pinfunction "1_1") (pintype "passive"))
      (node (ref "D1") (pin "2") (pintype "passive"))
      (node (ref "R9") (pin "1") (pinfunction "1_1") (pintype "passive"))
      (node (ref "U2") (pin "1") (pinfunction "VIN_1") (pintype "power_in"))
    )
    (net (code "129") (name "GND") (class "Default")
      (node (ref "C1") (pin "1") (pinfunction "1_1") (pintype "passive"))
      (node (ref "C10") (pin "1") (pinfunction "1_1") (pintype "passive"))
      (node (ref "C11") (pin "1") (pinfunction "1_1") (pintype "passive"))
      (node (ref "C12") (pin "2") (pinfunction "2_2") (pintype "passive"))
      (node (ref "C13") (pin "2") (pinfunction "2_2") (pintype "passive"))
      (node (ref "C14") (pin "2") (pinfunction "2_2") (pintype "passive"))
      (node (ref "C15") (pin "2") (pinfunction "2_2") (pintype "passive"))
      (node (ref "C16") (pin "1") (pinfunction "1_1") (pintype "passive"))
      (node (ref "C18") (pin "1") (pinfunction "1_1") (pintype "passive"))
      (node (ref "C19") (pin "1") (pinfunction "1_1") (pintype "passive"))
      (node (ref "C20") (pin "1") (pinfunction "1_1") (pintype "passive"))
      (node (ref "C21") (pin "1") (pinfunction "1_1") (pintype "passive"))
      (node (ref "C22") (pin "1") (pinfunction "1_1") (pintype "passive"))
      (node (ref "C23") (pin "1") (pinfunction "1_1") (pintype "passive"))
      (node (ref "C24") (pin "2") (pinfunction "2_2") (pintype "passive"))
      (node (ref "C25") (pin "1") (pinfunction "1_1") (pintype "passive"))
      (node (ref "C27") (pin "1") (pinfunction "1_1") (pintype "passive"))
      (node (ref "C28") (pin "1") (pinfunction "1_1") (pintype "passive"))
      (node (ref "C29") (pin "1") (pinfunction "1_1") (pintype "passive"))
      (node (ref "C3") (pin "2") (pinfunction "2_2") (pintype "passive"))
      (node (ref "C30") (pin "1") (pinfunction "1_1") (pintype "passive"))
      (node (ref "C31") (pin "1") (pinfunction "1_1") (pintype "passive"))
      (node (ref "C32") (pin "1") (pinfunction "1_1") (pintype "passive"))
      (node (ref "C33") (pin "1") (pinfunction "1_1") (pintype "passive"))
      (node (ref "C35") (pin "2") (pinfunction "2_2") (pintype "passive"))
      (node (ref "C36") (pin "1") (pinfunction "1_1") (pintype "passive"))
      (node (ref "C37") (pin "2") (pinfunction "2_2") (pintype "passive"))
      (node (ref "C38") (pin "2") (pinfunction "2_2") (pintype "passive"))
      (node (ref "C39") (pin "1") (pinfunction "1_1") (pintype "passive"))
      (node (ref "C4") (pin "2") (pinfunction "2_2") (pintype "passive"))
      (node (ref "C40") (pin "1") (pinfunction "1_1") (pintype "passive"))
      (node (ref "C41") (pin "1") (pinfunction "1_1") (pintype "passive"))
      (node (ref "C42") (pin "1") (pinfunction "1_1") (pintype "passive"))
      (node (ref "C43") (pin "1") (pinfunction "1_1") (pintype "passive"))
      (node (ref "C44") (pin "1") (pinfunction "1_1") (pintype "passive"))
      (node (ref "C5") (pin "1") (pinfunction "1_1") (pintype "passive"))
      (node (ref "C6") (pin "2") (pinfunction "2_2") (pintype "passive"))
      (node (ref "C7") (pin "1") (pinfunction "1_1") (pintype "passive"))
      (node (ref "C8") (pin "1") (pinfunction "1_1") (pintype "passive"))
      (node (ref "C9") (pin "1") (pinfunction "1_1") (pintype "passive"))
      (node (ref "D3") (pin "2") (pinfunction "B_2") (pintype "passive"))
      (node (ref "D5") (pin "2") (pinfunction "K_2") (pintype "passive"))
      (node (ref "D6") (pin "2") (pinfunction "K_2") (pintype "passive"))
      (node (ref "D7") (pin "2") (pinfunction "K_2") (pintype "passive"))
      (node (ref "H7") (pin "3") (pinfunction "3_3") (pintype "passive"))
      (node (ref "HD1") (pin "1") (pinfunction "1_1") (pintype "passive"))
      (node (ref "IC1") (pin "1") (pinfunction "ADJ/G_1") (pintype "passive"))
      (node (ref "IC2") (pin "1") (pinfunction "A0_1") (pintype "passive"))
      (node (ref "IC2") (pin "2") (pinfunction "A1_2") (pintype "passive"))
      (node (ref "IC2") (pin "3") (pinfunction "A2_3") (pintype "passive"))
      (node (ref "IC2") (pin "4") (pinfunction "GND_4") (pintype "power_in"))
      (node (ref "IC2") (pin "7") (pinfunction "WP_7") (pintype "passive"))
      (node (ref "OP1") (pin "3") (pinfunction "C_3") (pintype "passive"))
      (node (ref "OP10") (pin "3") (pinfunction "C_3") (pintype "passive"))
      (node (ref "OP12") (pin "3") (pinfunction "C_3") (pintype "passive"))
      (node (ref "OP3") (pin "3") (pinfunction "C_3") (pintype "passive"))
      (node (ref "OP4") (pin "3") (pinfunction "C_3") (pintype "passive"))
      (node (ref "OP6") (pin "3") (pinfunction "C_3") (pintype "passive"))
      (node (ref "OP7") (pin "3") (pinfunction "C_3") (pintype "passive"))
      (node (ref "OP9") (pin "3") (pinfunction "C_3") (pintype "passive"))
      (node (ref "RN1") (pin "1") (pinfunction "1_1") (pintype "passive"))
      (node (ref "S1") (pin "1") (pinfunction "1_1") (pintype "passive"))
      (node (ref "U1") (pin "1") (pinfunction "1_1") (pintype "passive"))
      (node (ref "U1") (pin "14") (pinfunction "14_14") (pintype "passive"))
      (node (ref "U1") (pin "31") (pinfunction "31_31") (pintype "passive"))
      (node (ref "U1") (pin "45") (pinfunction "45_45") (pintype "passive"))
      (node (ref "U1") (pin "58") (pinfunction "58_58") (pintype "passive"))
      (node (ref "U1") (pin "75") (pinfunction "75_75") (pintype "passive"))
      (node (ref "U2") (pin "0") (pinfunction "PAD_0") (pintype "passive"))
      (node (ref "U2") (pin "3") (pinfunction "GND_3") (pintype "power_in"))
      (node (ref "U2") (pin "5") (pinfunction "~{ON}/OFF_5") (pintype "input"))
      (node (ref "U3") (pin "7") (pinfunction "GND_7") (pintype "passive"))
      (node (ref "U4") (pin "7") (pinfunction "GND_7") (pintype "passive"))
      (node (ref "U5") (pin "10") (pinfunction "GND_10") (pintype "power_in"))
      (node (ref "U5") (pin "19") (pinfunction "OE_19") (pintype "passive"))
      (node (ref "U6") (pin "11") (pinfunction "GND_11") (pintype "passive"))
      (node (ref "U6") (pin "12") (pinfunction "GND_12") (pintype "passive"))
      (node (ref "U6") (pin "13") (pinfunction "GND_13") (pintype "passive"))
      (node (ref "U6") (pin "22") (pinfunction "~{OE}_22") (pintype "passive"))
      (node (ref "U7") (pin "11") (pinfunction "GND_11") (pintype "passive"))
      (node (ref "U7") (pin "12") (pinfunction "GND_12") (pintype "passive"))
      (node (ref "U7") (pin "13") (pinfunction "GND_13") (pintype "passive"))
      (node (ref "U7") (pin "22") (pinfunction "~{OE}_22") (pintype "passive"))
      (node (ref "U8") (pin "11") (pinfunction "GND_11") (pintype "passive"))
      (node (ref "U8") (pin "12") (pinfunction "GND_12") (pintype "passive"))
      (node (ref "U8") (pin "13") (pinfunction "GND_13") (pintype "passive"))
      (node (ref "U8") (pin "22") (pinfunction "~{OE}_22") (pintype "passive"))
    )
    (net (code "130") (name "G_Drive") (class "Default")
      (node (ref "C17") (pin "1") (pinfunction "1_1") (pintype "passive"))
      (node (ref "C2") (pin "1") (pinfunction "1_1") (pintype "passive"))
      (node (ref "C26") (pin "1") (pinfunction "1_1") (pintype "passive"))
      (node (ref "C34") (pin "1") (pinfunction "1_1") (pintype "passive"))
      (node (ref "D10") (pin "2") (pinfunction "K_2") (pintype "passive"))
      (node (ref "D11") (pin "2") (pinfunction "K_2") (pintype "passive"))
      (node (ref "D12") (pin "2") (pinfunction "K_2") (pintype "passive"))
      (node (ref "D13") (pin "2") (pinfunction "K_2") (pintype "passive"))
      (node (ref "D2") (pin "2") (pinfunction "K_2") (pintype "passive"))
      (node (ref "D4") (pin "2") (pinfunction "K_2") (pintype "passive"))
      (node (ref "D8") (pin "2") (pinfunction "K_2") (pintype "passive"))
      (node (ref "D9") (pin "2") (pinfunction "K_2") (pintype "passive"))
      (node (ref "H1") (pin "1") (pinfunction "1_1") (pintype "passive"))
      (node (ref "H2") (pin "1") (pinfunction "1_1") (pintype "passive"))
      (node (ref "H3") (pin "1") (pinfunction "1_1") (pintype "passive"))
      (node (ref "H4") (pin "1") (pinfunction "1_1") (pintype "passive"))
      (node (ref "H5") (pin "1") (pinfunction "1_1") (pintype "passive"))
      (node (ref "H6") (pin "1") (pinfunction "1_1") (pintype "passive"))
      (node (ref "HD11") (pin "4") (pinfunction "4_4") (pintype "passive"))
      (node (ref "HD2") (pin "4") (pinfunction "4_4") (pintype "passive"))
      (node (ref "HD5") (pin "1") (pinfunction "1_1") (pintype "passive"))
      (node (ref "HD7") (pin "4") (pinfunction "4_4") (pintype "passive"))
      (node (ref "HD9") (pin "4") (pinfunction "4_4") (pintype "passive"))
      (node (ref "OP1") (pin "2") (pinfunction "C_2") (pintype "passive"))
      (node (ref "OP10") (pin "2") (pinfunction "C_2") (pintype "passive"))
      (node (ref "OP11") (pin "5") (pinfunction "GND_5") (pintype "passive"))
      (node (ref "OP12") (pin "2") (pinfunction "C_2") (pintype "passive"))
      (node (ref "OP2") (pin "5") (pinfunction "GND_5") (pintype "passive"))
      (node (ref "OP3") (pin "2") (pinfunction "C_2") (pintype "passive"))
      (node (ref "OP4") (pin "2") (pinfunction "C_2") (pintype "passive"))
      (node (ref "OP5") (pin "5") (pinfunction "GND_5") (pintype "passive"))
      (node (ref "OP6") (pin "2") (pinfunction "C_2") (pintype "passive"))
      (node (ref "OP7") (pin "2") (pinfunction "C_2") (pintype "passive"))
      (node (ref "OP8") (pin "5") (pinfunction "GND_5") (pintype "passive"))
      (node (ref "OP9") (pin "2") (pinfunction "C_2") (pintype "passive"))
    )
    (net (code "131") (name "Net-(D1-Pad1)") (class "Default")
      (node (ref "D1") (pin "1") (pintype "passive"))
      (node (ref "F1") (pin "2") (pinfunction "2_2") (pintype "passive"))
    )
    (net (code "132") (name "Net-(D2-A)") (class "Default")
      (node (ref "D2") (pin "1") (pinfunction "A_1") (pintype "passive"))
      (node (ref "OP1") (pin "1") (pinfunction "A_1") (pintype "passive"))
      (node (ref "R1") (pin "1") (pinfunction "1_1") (pintype "passive"))
    )
    (net (code "133") (name "Net-(D3-a)") (class "Default")
      (node (ref "D3") (pin "1") (pinfunction "a_1") (pintype "passive"))
      (node (ref "L1") (pin "1") (pinfunction "1_1") (pintype "passive"))
      (node (ref "U2") (pin "2") (pinfunction "OUT_2") (pintype "power_in"))
    )
    (net (code "134") (name "Net-(D4-A)") (class "Default")
      (node (ref "D4") (pin "1") (pinfunction "A_1") (pintype "passive"))
      (node (ref "OP3") (pin "1") (pinfunction "A_1") (pintype "passive"))
      (node (ref "R4") (pin "1") (pinfunction "1_1") (pintype "passive"))
    )
    (net (code "135") (name "Net-(D5-A)") (class "Default")
      (node (ref "D5") (pin "1") (pinfunction "A_1") (pintype "passive"))
      (node (ref "R7") (pin "2") (pinfunction "2_2") (pintype "passive"))
    )
    (net (code "136") (name "Net-(D6-A)") (class "Default")
      (node (ref "D6") (pin "1") (pinfunction "A_1") (pintype "passive"))
      (node (ref "R8") (pin "2") (pinfunction "2_2") (pintype "passive"))
    )
    (net (code "137") (name "Net-(D7-A)") (class "Default")
      (node (ref "D7") (pin "1") (pinfunction "A_1") (pintype "passive"))
      (node (ref "R9") (pin "2") (pinfunction "2_2") (pintype "passive"))
    )
    (net (code "138") (name "Net-(D8-A)") (class "Default")
      (node (ref "D8") (pin "1") (pinfunction "A_1") (pintype "passive"))
      (node (ref "OP4") (pin "1") (pinfunction "A_1") (pintype "passive"))
      (node (ref "R10") (pin "1") (pinfunction "1_1") (pintype "passive"))
    )
    (net (code "139") (name "Net-(D9-A)") (class "Default")
      (node (ref "D9") (pin "1") (pinfunction "A_1") (pintype "passive"))
      (node (ref "OP6") (pin "1") (pinfunction "A_1") (pintype "passive"))
      (node (ref "R13") (pin "1") (pinfunction "1_1") (pintype "passive"))
    )
    (net (code "140") (name "Net-(D10-A)") (class "Default")
      (node (ref "D10") (pin "1") (pinfunction "A_1") (pintype "passive"))
      (node (ref "OP7") (pin "1") (pinfunction "A_1") (pintype "passive"))
      (node (ref "R17") (pin "1") (pinfunction "1_1") (pintype "passive"))
    )
    (net (code "141") (name "Net-(D11-A)") (class "Default")
      (node (ref "D11") (pin "1") (pinfunction "A_1") (pintype "passive"))
      (node (ref "OP9") (pin "1") (pinfunction "A_1") (pintype "passive"))
      (node (ref "R18") (pin "1") (pinfunction "1_1") (pintype "passive"))
    )
    (net (code "142") (name "Net-(D12-A)") (class "Default")
      (node (ref "D12") (pin "1") (pinfunction "A_1") (pintype "passive"))
      (node (ref "OP10") (pin "1") (pinfunction "A_1") (pintype "passive"))
      (node (ref "R25") (pin "1") (pinfunction "1_1") (pintype "passive"))
    )
    (net (code "143") (name "Net-(D13-A)") (class "Default")
      (node (ref "D13") (pin "1") (pinfunction "A_1") (pintype "passive"))
      (node (ref "OP12") (pin "1") (pinfunction "A_1") (pintype "passive"))
      (node (ref "R27") (pin "1") (pinfunction "1_1") (pintype "passive"))
    )
    (net (code "144") (name "Net-(F1-Pad1)") (class "Default")
      (node (ref "F1") (pin "1") (pinfunction "1_1") (pintype "passive"))
      (node (ref "HD1") (pin "2") (pinfunction "2_2") (pintype "passive"))
    )
    (net (code "145") (name "Net-(OP2-C1)") (class "Default")
      (node (ref "OP2") (pin "2") (pinfunction "C1_2") (pintype "passive"))
      (node (ref "R3") (pin "2") (pinfunction "2_2") (pintype "passive"))
    )
    (net (code "146") (name "Net-(OP2-C2)") (class "Default")
      (node (ref "OP2") (pin "3") (pinfunction "C2_3") (pintype "passive"))
      (node (ref "R5") (pin "2") (pinfunction "2_2") (pintype "passive"))
    )
    (net (code "147") (name "Net-(OP5-C1)") (class "Default")
      (node (ref "OP5") (pin "2") (pinfunction "C1_2") (pintype "passive"))
      (node (ref "R12") (pin "2") (pinfunction "2_2") (pintype "passive"))
    )
    (net (code "148") (name "Net-(OP5-C2)") (class "Default")
      (node (ref "OP5") (pin "3") (pinfunction "C2_3") (pintype "passive"))
      (node (ref "R14") (pin "2") (pinfunction "2_2") (pintype "passive"))
    )
    (net (code "149") (name "Net-(OP8-C1)") (class "Default")
      (node (ref "OP8") (pin "2") (pinfunction "C1_2") (pintype "passive"))
      (node (ref "R20") (pin "2") (pinfunction "2_2") (pintype "passive"))
    )
    (net (code "150") (name "Net-(OP8-C2)") (class "Default")
      (node (ref "OP8") (pin "3") (pinfunction "C2_3") (pintype "passive"))
      (node (ref "R21") (pin "2") (pinfunction "2_2") (pintype "passive"))
    )
    (net (code "151") (name "Net-(OP11-C1)") (class "Default")
      (node (ref "OP11") (pin "2") (pinfunction "C1_2") (pintype "passive"))
      (node (ref "R28") (pin "2") (pinfunction "2_2") (pintype "passive"))
    )
    (net (code "152") (name "Net-(OP11-C2)") (class "Default")
      (node (ref "OP11") (pin "3") (pinfunction "C2_3") (pintype "passive"))
      (node (ref "R29") (pin "2") (pinfunction "2_2") (pintype "passive"))
    )
    (net (code "153") (name "VDrive") (class "Default")
      (node (ref "C17") (pin "2") (pinfunction "2_2") (pintype "passive"))
      (node (ref "C2") (pin "2") (pinfunction "2_2") (pintype "passive"))
      (node (ref "C26") (pin "2") (pinfunction "2_2") (pintype "passive"))
      (node (ref "C34") (pin "2") (pinfunction "2_2") (pintype "passive"))
      (node (ref "H1") (pin "2") (pinfunction "2_2") (pintype "passive"))
      (node (ref "H2") (pin "2") (pinfunction "2_2") (pintype "passive"))
      (node (ref "H3") (pin "2") (pinfunction "2_2") (pintype "passive"))
      (node (ref "H4") (pin "2") (pinfunction "2_2") (pintype "passive"))
      (node (ref "H5") (pin "2") (pinfunction "2_2") (pintype "passive"))
      (node (ref "H6") (pin "2") (pinfunction "2_2") (pintype "passive"))
      (node (ref "HD10") (pin "2") (pinfunction "2_2") (pintype "passive"))
      (node (ref "HD11") (pin "1") (pinfunction "1_1") (pintype "passive"))
      (node (ref "HD12") (pin "2") (pinfunction "2_2") (pintype "passive"))
      (node (ref "HD2") (pin "1") (pinfunction "1_1") (pintype "passive"))
      (node (ref "HD5") (pin "2") (pinfunction "2_2") (pintype "passive"))
      (node (ref "HD7") (pin "1") (pinfunction "1_1") (pintype "passive"))
      (node (ref "HD9") (pin "1") (pinfunction "1_1") (pintype "passive"))
      (node (ref "OP11") (pin "8") (pinfunction "VCC_8") (pintype "passive"))
      (node (ref "OP2") (pin "8") (pinfunction "VCC_8") (pintype "passive"))
      (node (ref "OP5") (pin "8") (pinfunction "VCC_8") (pintype "passive"))
      (node (ref "OP8") (pin "8") (pinfunction "VCC_8") (pintype "passive"))
      (node (ref "R11") (pin "1") (pinfunction "1_1") (pintype "passive"))
      (node (ref "R15") (pin "1") (pinfunction "1_1") (pintype "passive"))
      (node (ref "R19") (pin "1") (pinfunction "1_1") (pintype "passive"))
      (node (ref "R2") (pin "1") (pinfunction "1_1") (pintype "passive"))
      (node (ref "R22") (pin "1") (pinfunction "1_1") (pintype "passive"))
      (node (ref "R26") (pin "1") (pinfunction "1_1") (pintype "passive"))
      (node (ref "R30") (pin "1") (pinfunction "1_1") (pintype "passive"))
      (node (ref "R6") (pin "1") (pinfunction "1_1") (pintype "passive"))
    )
    (net (code "154") (name "unconnected-(U1-Pad12)") (class "Default")
      (node (ref "U1") (pin "12") (pinfunction "12_12") (pintype "passive"))
    )
    (net (code "155") (name "unconnected-(U1-Pad52)") (class "Default")
      (node (ref "U1") (pin "52") (pinfunction "52_52") (pintype "passive+no_connect"))
    )
    (net (code "156") (name "unconnected-(U3-7-Pad8)") (class "Default")
      (node (ref "U3") (pin "8") (pinfunction "7_8") (pintype "passive"))
    )
    (net (code "157") (name "unconnected-(U3-8-Pad9)") (class "Default")
      (node (ref "U3") (pin "9") (pinfunction "8_9") (pintype "passive"))
    )
    (net (code "158") (name "unconnected-(U3-Pad5)") (class "Default")
      (node (ref "U3") (pin "5") (pintype "passive"))
    )
    (net (code "159") (name "unconnected-(U3-Pad6)") (class "Default")
      (node (ref "U3") (pin "6") (pintype "passive"))
    )
    (net (code "160") (name "unconnected-(U4-7-Pad8)") (class "Default")
      (node (ref "U4") (pin "8") (pinfunction "7_8") (pintype "passive"))
    )
    (net (code "161") (name "unconnected-(U4-8-Pad9)") (class "Default")
      (node (ref "U4") (pin "9") (pinfunction "8_9") (pintype "passive"))
    )
    (net (code "162") (name "unconnected-(U4-Pad5)") (class "Default")
      (node (ref "U4") (pin "5") (pintype "passive"))
    )
    (net (code "163") (name "unconnected-(U4-Pad6)") (class "Default")
      (node (ref "U4") (pin "6") (pintype "passive"))
    )
    (net (code "164") (name "unconnected-(U6-A4-Pad7)") (class "Default")
      (node (ref "U6") (pin "7") (pinfunction "A4_7") (pintype "passive"))
    )
    (net (code "165") (name "unconnected-(U6-A5-Pad8)") (class "Default")
      (node (ref "U6") (pin "8") (pinfunction "A5_8") (pintype "passive"))
    )
    (net (code "166") (name "unconnected-(U6-A6-Pad9)") (class "Default")
      (node (ref "U6") (pin "9") (pinfunction "A6_9") (pintype "passive"))
    )
    (net (code "167") (name "unconnected-(U6-A7-Pad10)") (class "Default")
      (node (ref "U6") (pin "10") (pinfunction "A7_10") (pintype "passive"))
    )
    (net (code "168") (name "unconnected-(U6-B4-Pad17)") (class "Default")
      (node (ref "U6") (pin "17") (pinfunction "B4_17") (pintype "passive"))
    )
    (net (code "169") (name "unconnected-(U6-B5-Pad16)") (class "Default")
      (node (ref "U6") (pin "16") (pinfunction "B5_16") (pintype "passive"))
    )
    (net (code "170") (name "unconnected-(U6-B6-Pad15)") (class "Default")
      (node (ref "U6") (pin "15") (pinfunction "B6_15") (pintype "passive"))
    )
    (net (code "171") (name "unconnected-(U6-B7-Pad14)") (class "Default")
      (node (ref "U6") (pin "14") (pinfunction "B7_14") (pintype "passive"))
    )
    (net (code "172") (name "unconnected-(U7-A4-Pad7)") (class "Default")
      (node (ref "U7") (pin "7") (pinfunction "A4_7") (pintype "passive"))
    )
    (net (code "173") (name "unconnected-(U7-A5-Pad8)") (class "Default")
      (node (ref "U7") (pin "8") (pinfunction "A5_8") (pintype "passive"))
    )
    (net (code "174") (name "unconnected-(U7-A6-Pad9)") (class "Default")
      (node (ref "U7") (pin "9") (pinfunction "A6_9") (pintype "passive"))
    )
    (net (code "175") (name "unconnected-(U7-A7-Pad10)") (class "Default")
      (node (ref "U7") (pin "10") (pinfunction "A7_10") (pintype "passive"))
    )
    (net (code "176") (name "unconnected-(U7-B4-Pad17)") (class "Default")
      (node (ref "U7") (pin "17") (pinfunction "B4_17") (pintype "passive"))
    )
    (net (code "177") (name "unconnected-(U7-B5-Pad16)") (class "Default")
      (node (ref "U7") (pin "16") (pinfunction "B5_16") (pintype "passive"))
    )
    (net (code "178") (name "unconnected-(U7-B6-Pad15)") (class "Default")
      (node (ref "U7") (pin "15") (pinfunction "B6_15") (pintype "passive"))
    )
    (net (code "179") (name "unconnected-(U7-B7-Pad14)") (class "Default")
      (node (ref "U7") (pin "14") (pinfunction "B7_14") (pintype "passive"))
    )
  )
)
